# axiom_beta_sensor_cmv12000_tht.net
KiCad netlist of a schematic drawn in EAGLE
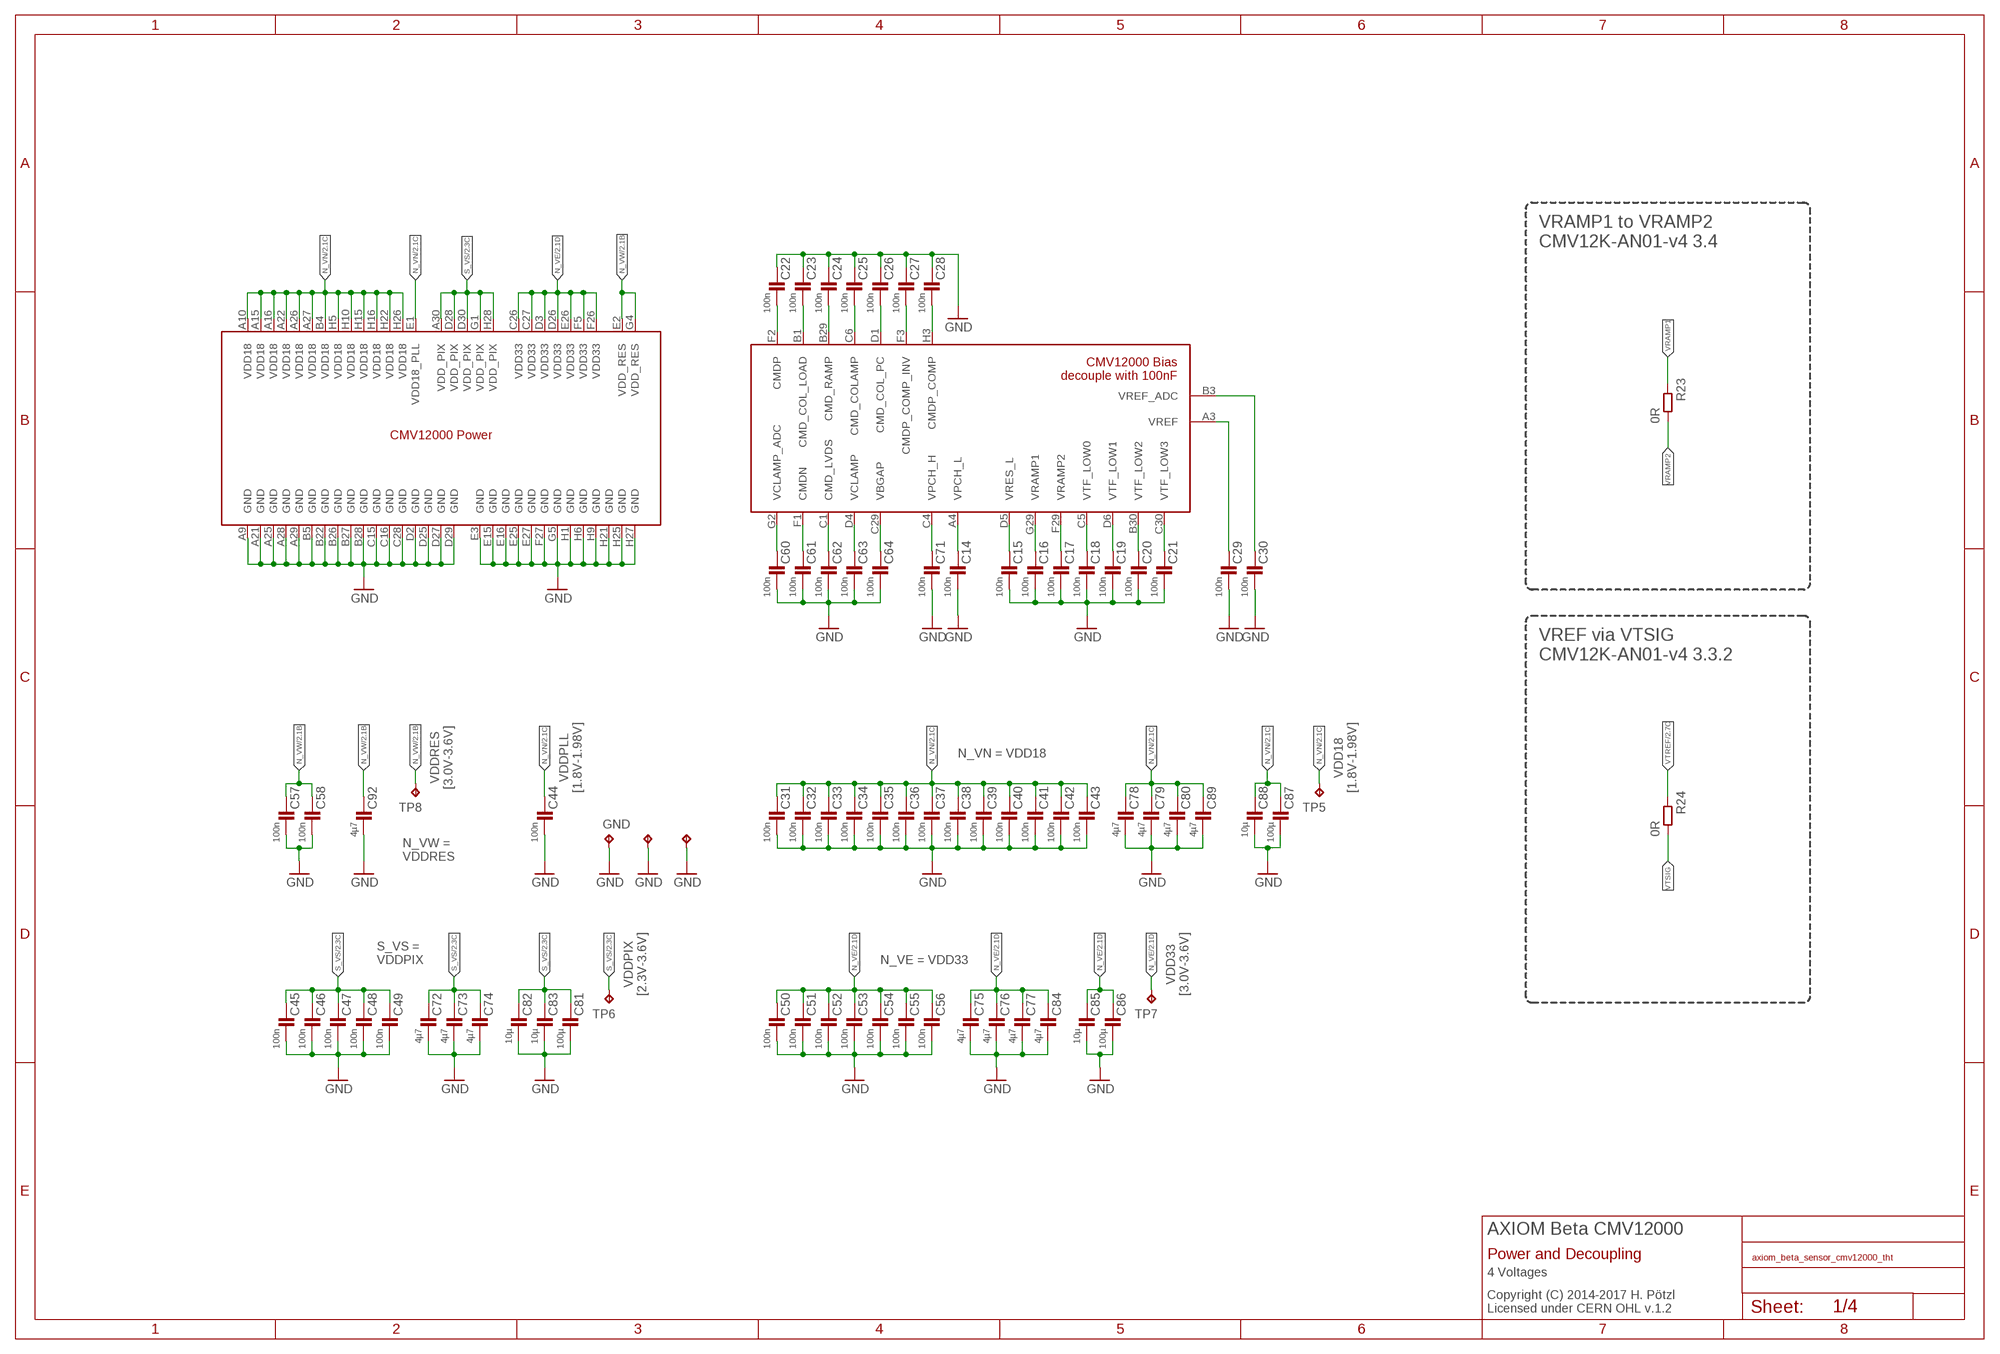
[diagram p0: schematic, sheet 1]
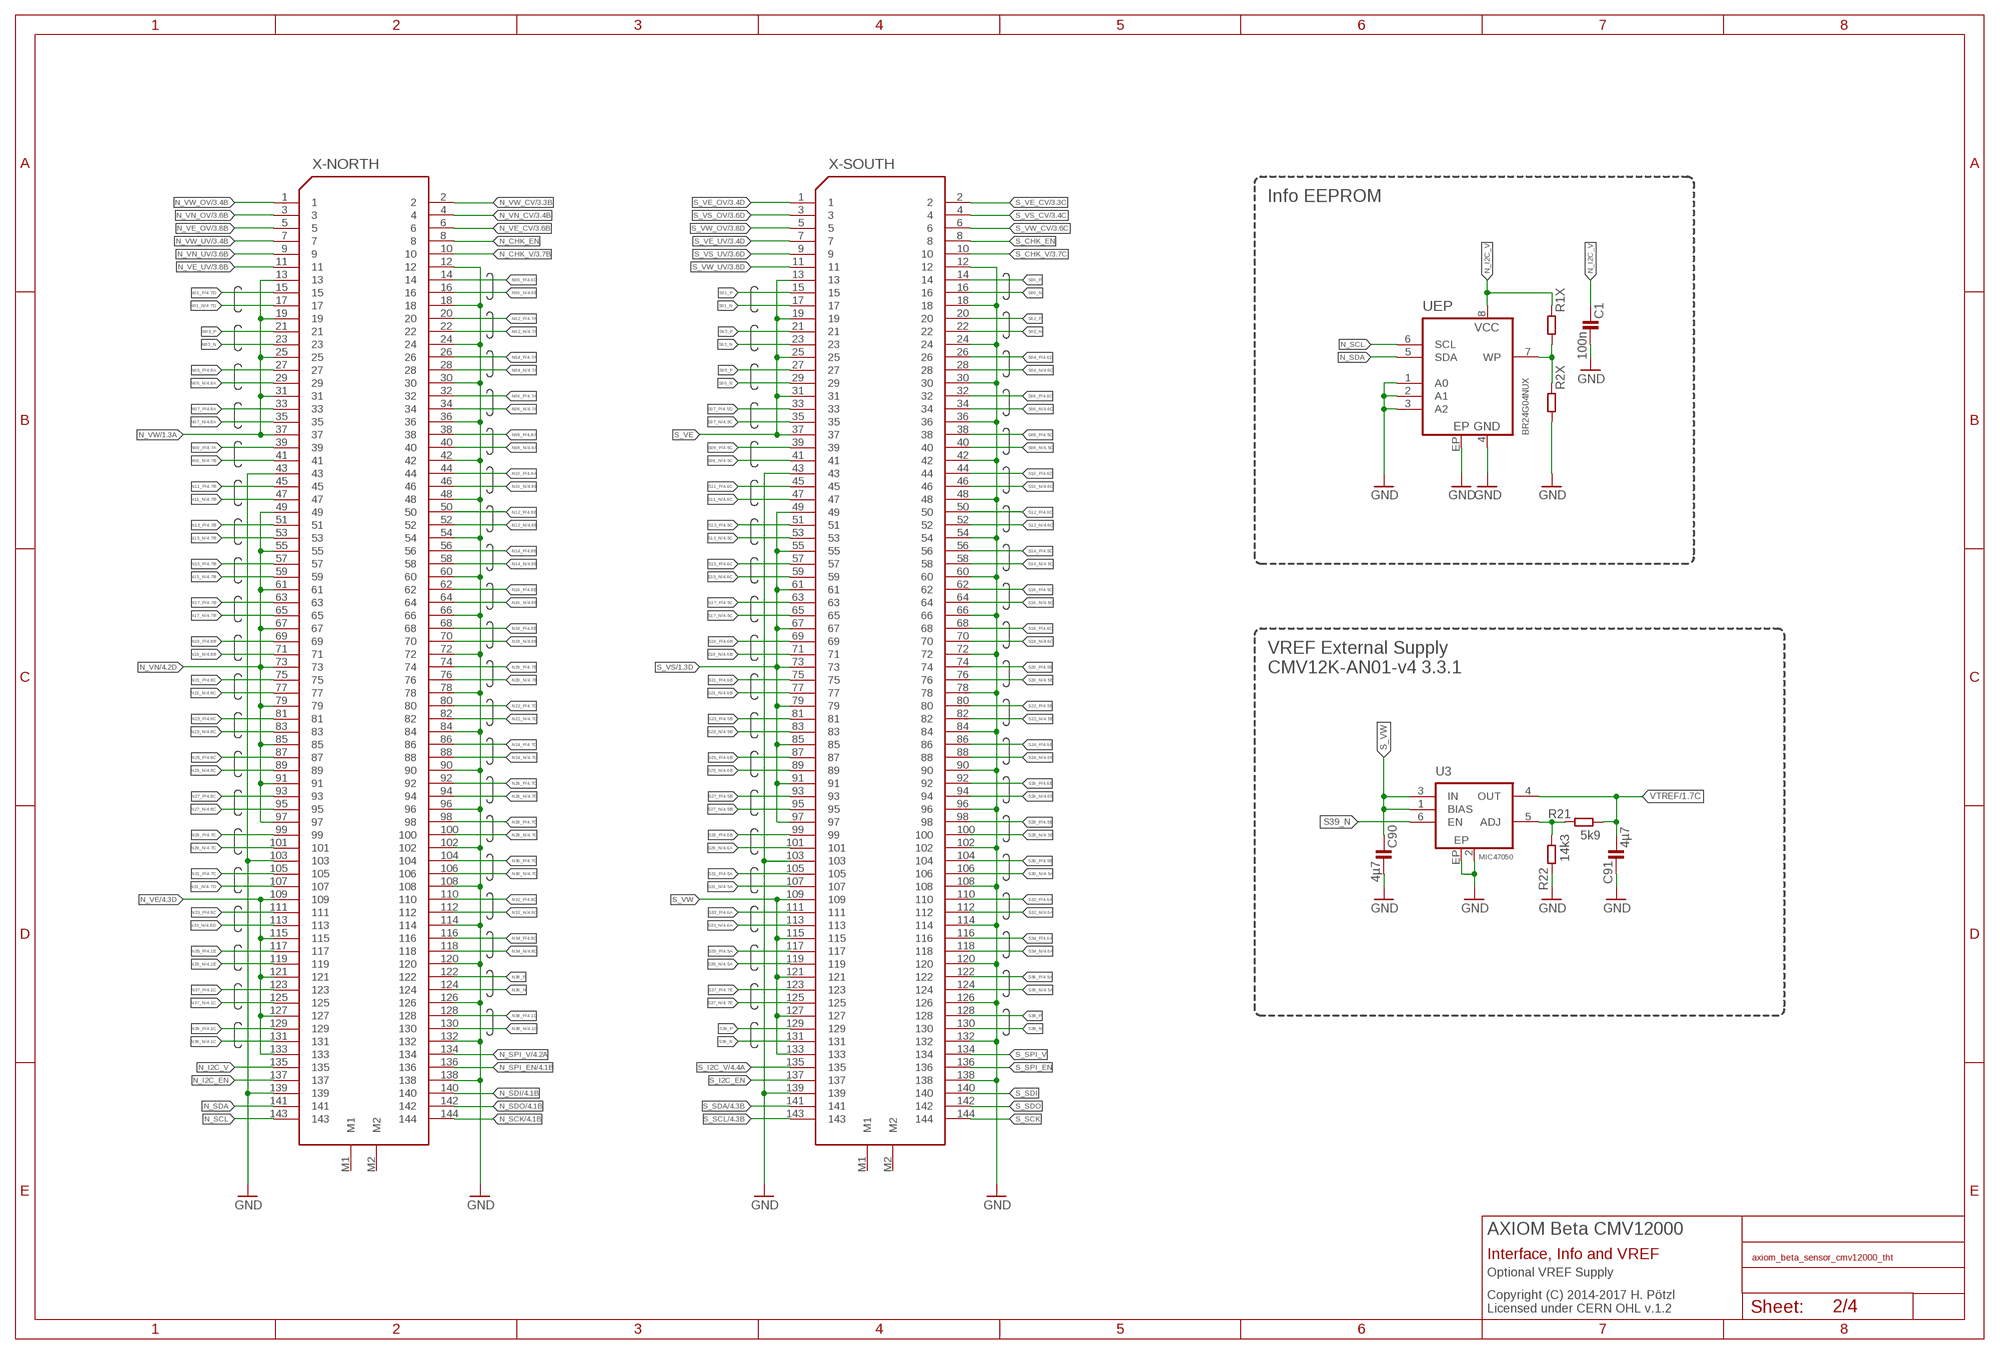
[diagram p1: schematic, sheet 2]
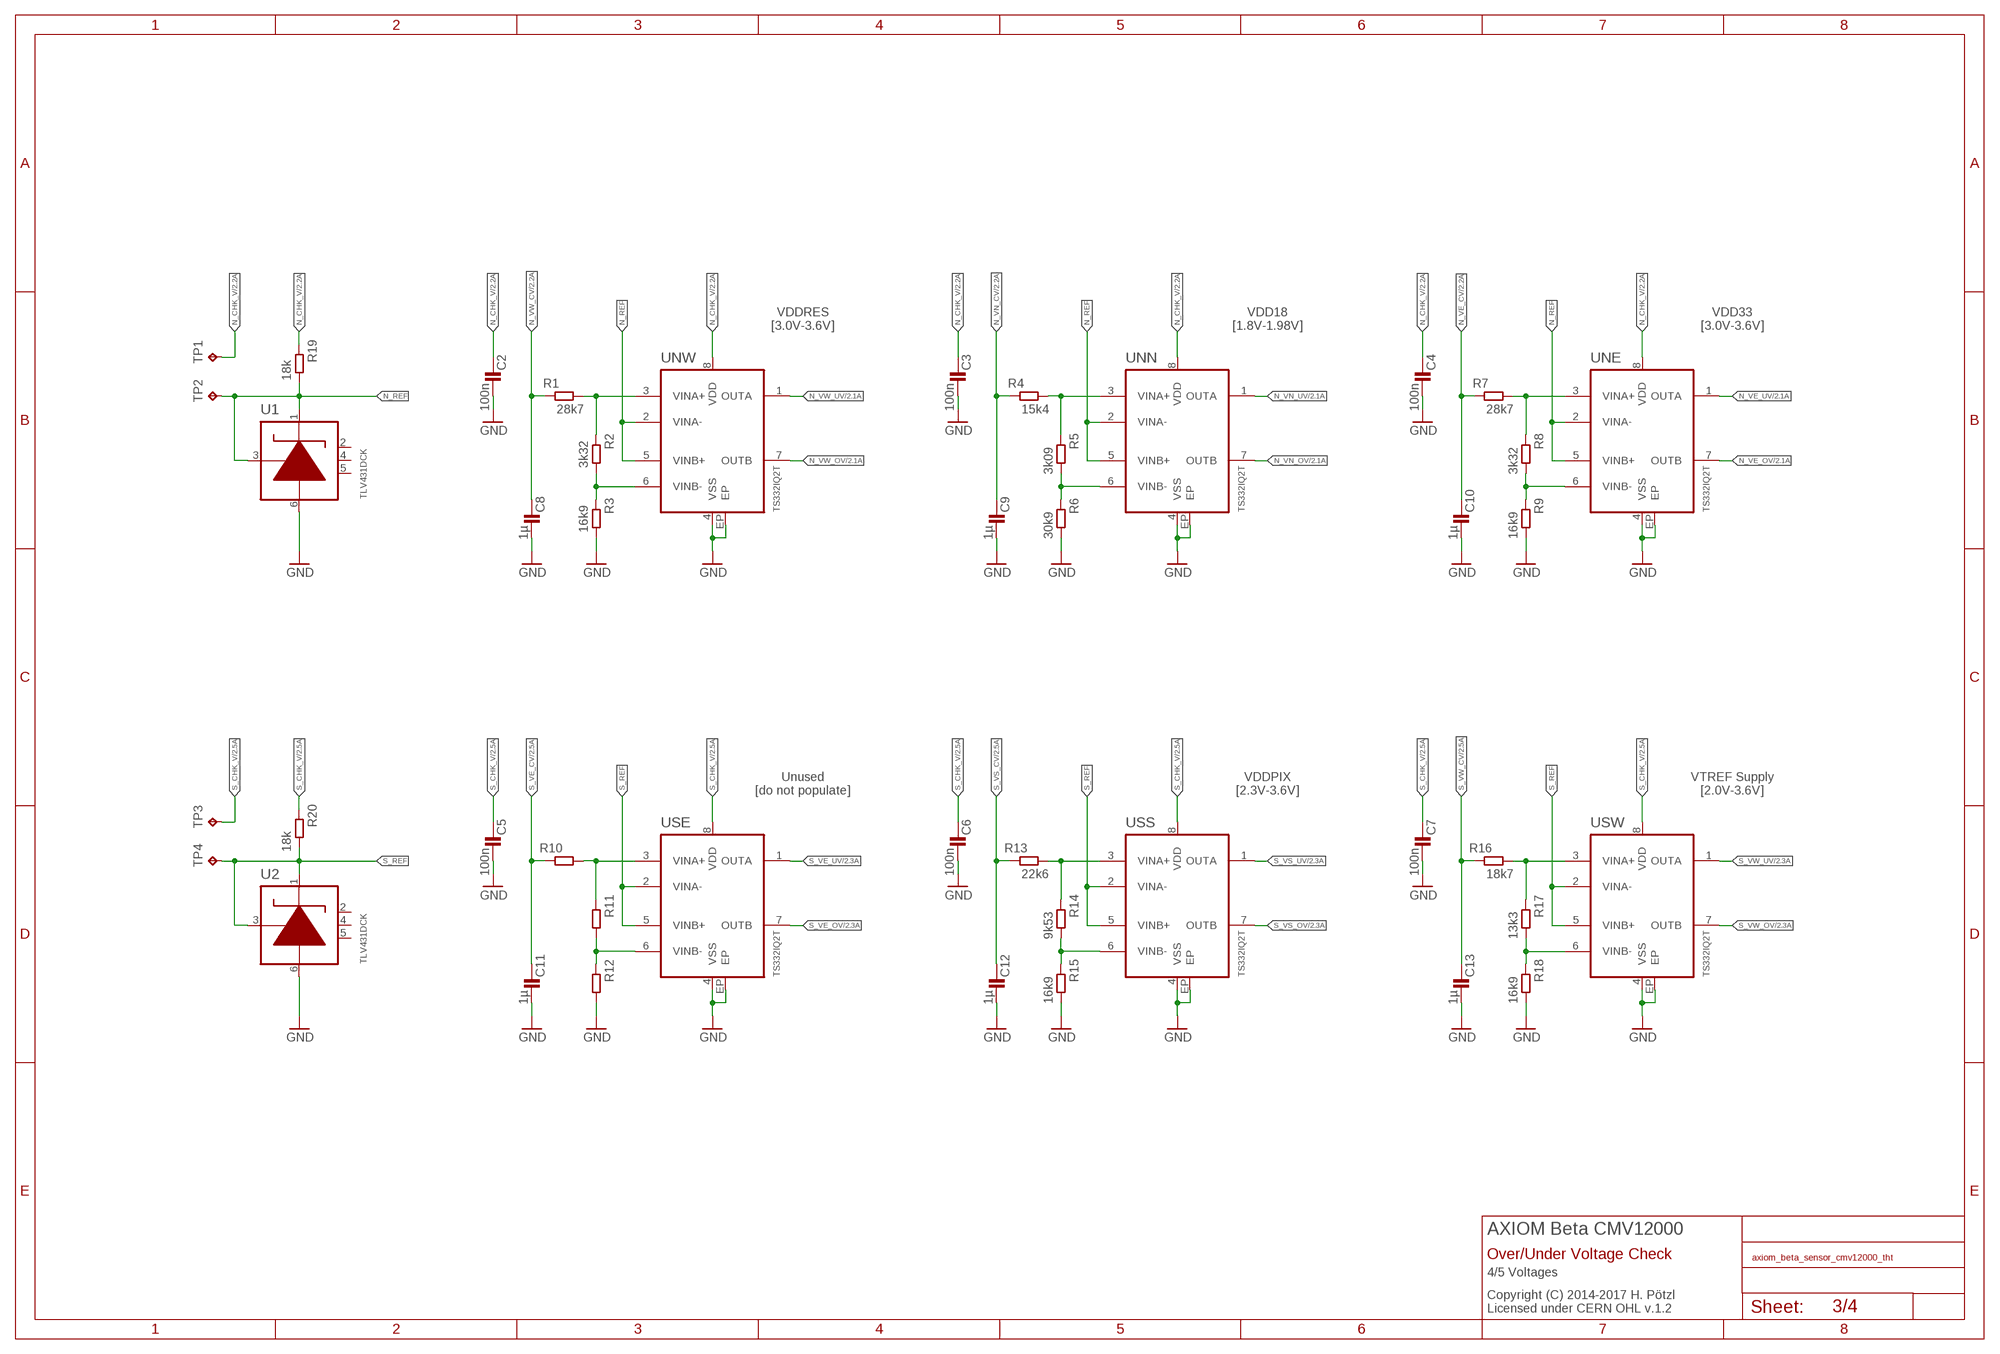
[diagram p2: schematic, sheet 3]
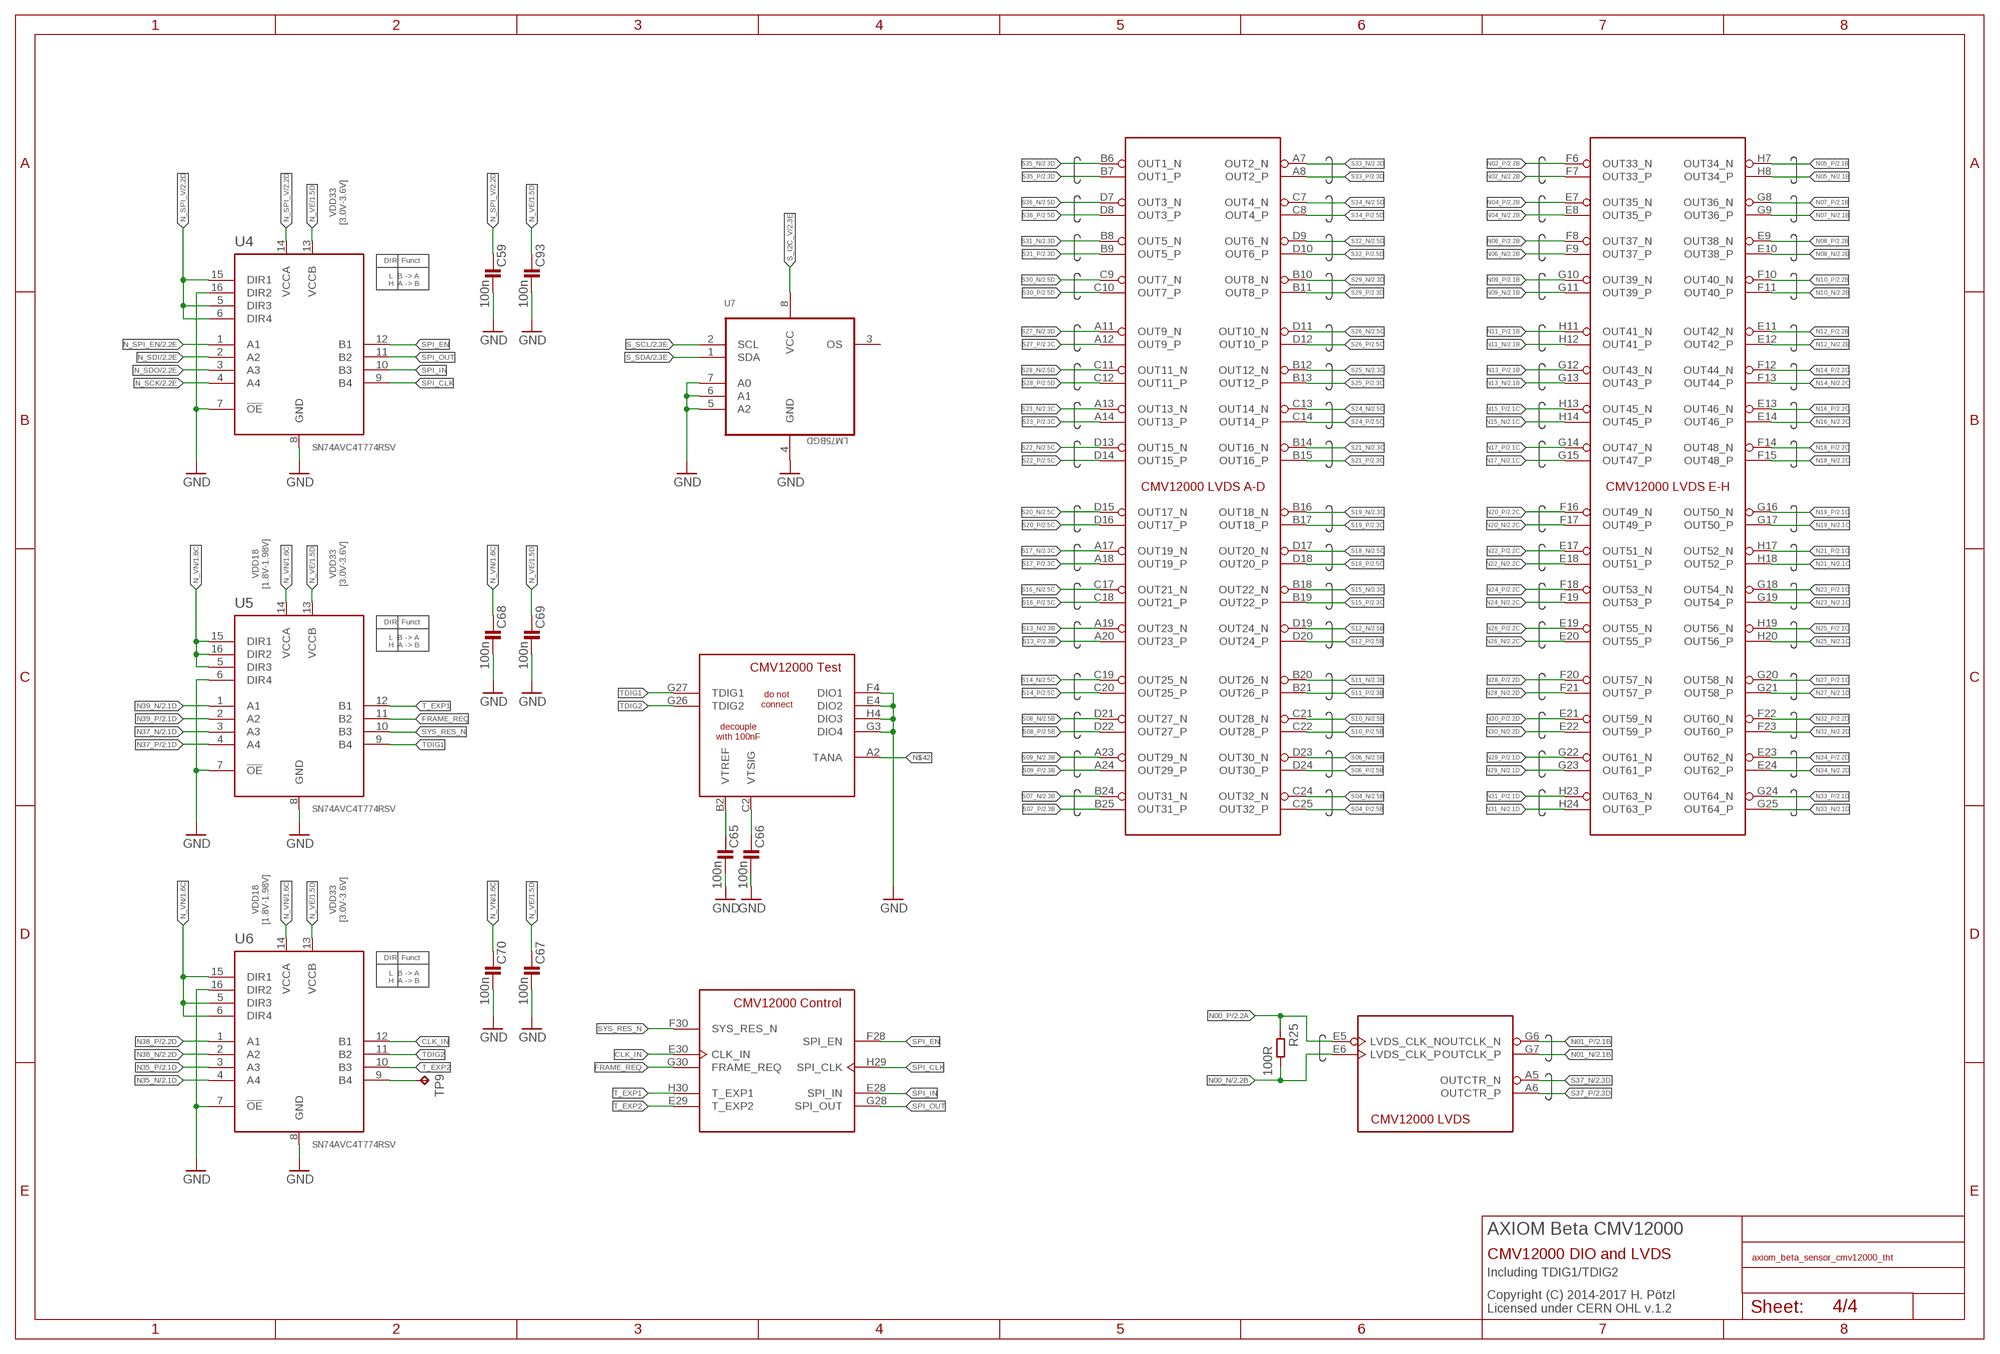
[diagram p3: schematic, sheet 4]

(export (version "E")
  (design (tool "Eeschema 10.0.6"))
  (components
    (comp (ref "C1")
      (value "100n")
      (footprint "eagle-import:0402-C")
      (libsource (lib "eagle-import") (part "C0402-C"))
    )
    (comp (ref "C90")
      (value "4µ7")
      (footprint "eagle-import:0402-C")
      (libsource (lib "eagle-import") (part "C0402-C"))
    )
    (comp (ref "C91")
      (value "4µ7")
      (footprint "eagle-import:0402-C")
      (libsource (lib "eagle-import") (part "C0402-C"))
    )
    (comp (ref "R1X")
      (value "R0402-C")
      (footprint "eagle-import:0402-C")
      (libsource (lib "eagle-import") (part "R0402-C"))
    )
    (comp (ref "R2X")
      (value "R0402-C")
      (footprint "eagle-import:0402-C")
      (libsource (lib "eagle-import") (part "R0402-C"))
    )
    (comp (ref "R21")
      (value "5k9")
      (footprint "eagle-import:0402-C")
      (libsource (lib "eagle-import") (part "R0402-C"))
    )
    (comp (ref "R22")
      (value "14k3")
      (footprint "eagle-import:0402-C")
      (libsource (lib "eagle-import") (part "R0402-C"))
    )
    (comp (ref "U3")
      (value "MIC47050")
      (footprint "eagle-import:MLF-6")
      (libsource (lib "eagle-import") (part "MIC47050-ADJ"))
    )
    (comp (ref "UEP")
      (value "BR24G04NUX")
      (footprint "eagle-import:DFN200X300X100-9N")
      (libsource (lib "eagle-import") (part "BR24G04NUX"))
    )
    (comp (ref "X-NORTH")
      (value "FX10-144P")
      (footprint "eagle-import:FX10A-144P")
      (libsource (lib "eagle-import") (part "FX10-144P"))
    )
    (comp (ref "X-SOUTH")
      (value "FX10-144P")
      (footprint "eagle-import:FX10A-144P")
      (libsource (lib "eagle-import") (part "FX10-144P"))
    )
    (comp (ref "C14")
      (value "100n")
      (footprint "eagle-import:0402-C")
      (libsource (lib "eagle-import") (part "C0402-C"))
    )
    (comp (ref "C15")
      (value "100n")
      (footprint "eagle-import:0402-C")
      (libsource (lib "eagle-import") (part "C0402-C"))
    )
    (comp (ref "C16")
      (value "100n")
      (footprint "eagle-import:0402-C")
      (libsource (lib "eagle-import") (part "C0402-C"))
    )
    (comp (ref "C17")
      (value "100n")
      (footprint "eagle-import:0402-C")
      (libsource (lib "eagle-import") (part "C0402-C"))
    )
    (comp (ref "C18")
      (value "100n")
      (footprint "eagle-import:0402-C")
      (libsource (lib "eagle-import") (part "C0402-C"))
    )
    (comp (ref "C19")
      (value "100n")
      (footprint "eagle-import:0402-C")
      (libsource (lib "eagle-import") (part "C0402-C"))
    )
    (comp (ref "C20")
      (value "100n")
      (footprint "eagle-import:0402-C")
      (libsource (lib "eagle-import") (part "C0402-C"))
    )
    (comp (ref "C21")
      (value "100n")
      (footprint "eagle-import:0402-C")
      (libsource (lib "eagle-import") (part "C0402-C"))
    )
    (comp (ref "C22")
      (value "100n")
      (footprint "eagle-import:0402-C")
      (libsource (lib "eagle-import") (part "C0402-C"))
    )
    (comp (ref "C23")
      (value "100n")
      (footprint "eagle-import:0402-C")
      (libsource (lib "eagle-import") (part "C0402-C"))
    )
    (comp (ref "C24")
      (value "100n")
      (footprint "eagle-import:0402-C")
      (libsource (lib "eagle-import") (part "C0402-C"))
    )
    (comp (ref "C25")
      (value "100n")
      (footprint "eagle-import:0402-C")
      (libsource (lib "eagle-import") (part "C0402-C"))
    )
    (comp (ref "C26")
      (value "100n")
      (footprint "eagle-import:0402-C")
      (libsource (lib "eagle-import") (part "C0402-C"))
    )
    (comp (ref "C27")
      (value "100n")
      (footprint "eagle-import:0402-C")
      (libsource (lib "eagle-import") (part "C0402-C"))
    )
    (comp (ref "C28")
      (value "100n")
      (footprint "eagle-import:0402-C")
      (libsource (lib "eagle-import") (part "C0402-C"))
    )
    (comp (ref "C29")
      (value "100n")
      (footprint "eagle-import:0402-C")
      (libsource (lib "eagle-import") (part "C0402-C"))
    )
    (comp (ref "C30")
      (value "100n")
      (footprint "eagle-import:0402-C")
      (libsource (lib "eagle-import") (part "C0402-C"))
    )
    (comp (ref "C31")
      (value "100n")
      (footprint "eagle-import:0402-C")
      (libsource (lib "eagle-import") (part "C0402-C"))
    )
    (comp (ref "C32")
      (value "100n")
      (footprint "eagle-import:0402-C")
      (libsource (lib "eagle-import") (part "C0402-C"))
    )
    (comp (ref "C33")
      (value "100n")
      (footprint "eagle-import:0402-C")
      (libsource (lib "eagle-import") (part "C0402-C"))
    )
    (comp (ref "C34")
      (value "100n")
      (footprint "eagle-import:0402-C")
      (libsource (lib "eagle-import") (part "C0402-C"))
    )
    (comp (ref "C35")
      (value "100n")
      (footprint "eagle-import:0402-C")
      (libsource (lib "eagle-import") (part "C0402-C"))
    )
    (comp (ref "C36")
      (value "100n")
      (footprint "eagle-import:0402-C")
      (libsource (lib "eagle-import") (part "C0402-C"))
    )
    (comp (ref "C37")
      (value "100n")
      (footprint "eagle-import:0402-C")
      (libsource (lib "eagle-import") (part "C0402-C"))
    )
    (comp (ref "C38")
      (value "100n")
      (footprint "eagle-import:0402-C")
      (libsource (lib "eagle-import") (part "C0402-C"))
    )
    (comp (ref "C39")
      (value "100n")
      (footprint "eagle-import:0402-C")
      (libsource (lib "eagle-import") (part "C0402-C"))
    )
    (comp (ref "C40")
      (value "100n")
      (footprint "eagle-import:0402-C")
      (libsource (lib "eagle-import") (part "C0402-C"))
    )
    (comp (ref "C41")
      (value "100n")
      (footprint "eagle-import:0402-C")
      (libsource (lib "eagle-import") (part "C0402-C"))
    )
    (comp (ref "C42")
      (value "100n")
      (footprint "eagle-import:0402-C")
      (libsource (lib "eagle-import") (part "C0402-C"))
    )
    (comp (ref "C43")
      (value "100n")
      (footprint "eagle-import:0402-C")
      (libsource (lib "eagle-import") (part "C0402-C"))
    )
    (comp (ref "C44")
      (value "100n")
      (footprint "eagle-import:0402-C")
      (libsource (lib "eagle-import") (part "C0402-C"))
    )
    (comp (ref "C45")
      (value "100n")
      (footprint "eagle-import:0402-C")
      (libsource (lib "eagle-import") (part "C0402-C"))
    )
    (comp (ref "C46")
      (value "100n")
      (footprint "eagle-import:0402-C")
      (libsource (lib "eagle-import") (part "C0402-C"))
    )
    (comp (ref "C47")
      (value "100n")
      (footprint "eagle-import:0402-C")
      (libsource (lib "eagle-import") (part "C0402-C"))
    )
    (comp (ref "C48")
      (value "100n")
      (footprint "eagle-import:0402-C")
      (libsource (lib "eagle-import") (part "C0402-C"))
    )
    (comp (ref "C49")
      (value "100n")
      (footprint "eagle-import:0402-C")
      (libsource (lib "eagle-import") (part "C0402-C"))
    )
    (comp (ref "C50")
      (value "100n")
      (footprint "eagle-import:0402-C")
      (libsource (lib "eagle-import") (part "C0402-C"))
    )
    (comp (ref "C51")
      (value "100n")
      (footprint "eagle-import:0402-C")
      (libsource (lib "eagle-import") (part "C0402-C"))
    )
    (comp (ref "C52")
      (value "100n")
      (footprint "eagle-import:0402-C")
      (libsource (lib "eagle-import") (part "C0402-C"))
    )
    (comp (ref "C53")
      (value "100n")
      (footprint "eagle-import:0402-C")
      (libsource (lib "eagle-import") (part "C0402-C"))
    )
    (comp (ref "C54")
      (value "100n")
      (footprint "eagle-import:0402-C")
      (libsource (lib "eagle-import") (part "C0402-C"))
    )
    (comp (ref "C55")
      (value "100n")
      (footprint "eagle-import:0402-C")
      (libsource (lib "eagle-import") (part "C0402-C"))
    )
    (comp (ref "C56")
      (value "100n")
      (footprint "eagle-import:0402-C")
      (libsource (lib "eagle-import") (part "C0402-C"))
    )
    (comp (ref "C57")
      (value "100n")
      (footprint "eagle-import:0402-C")
      (libsource (lib "eagle-import") (part "C0402-C"))
    )
    (comp (ref "C58")
      (value "100n")
      (footprint "eagle-import:0402-C")
      (libsource (lib "eagle-import") (part "C0402-C"))
    )
    (comp (ref "C60")
      (value "100n")
      (footprint "eagle-import:0402-C")
      (libsource (lib "eagle-import") (part "C0402-C"))
    )
    (comp (ref "C61")
      (value "100n")
      (footprint "eagle-import:0402-C")
      (libsource (lib "eagle-import") (part "C0402-C"))
    )
    (comp (ref "C62")
      (value "100n")
      (footprint "eagle-import:0402-C")
      (libsource (lib "eagle-import") (part "C0402-C"))
    )
    (comp (ref "C63")
      (value "100n")
      (footprint "eagle-import:0402-C")
      (libsource (lib "eagle-import") (part "C0402-C"))
    )
    (comp (ref "C64")
      (value "100n")
      (footprint "eagle-import:0402-C")
      (libsource (lib "eagle-import") (part "C0402-C"))
    )
    (comp (ref "C71")
      (value "100n")
      (footprint "eagle-import:0402-C")
      (libsource (lib "eagle-import") (part "C0402-C"))
    )
    (comp (ref "C72")
      (value "4µ7")
      (footprint "eagle-import:0402-B")
      (libsource (lib "eagle-import") (part "C0402-B"))
    )
    (comp (ref "C73")
      (value "4µ7")
      (footprint "eagle-import:0402-C")
      (libsource (lib "eagle-import") (part "C0402-C"))
    )
    (comp (ref "C74")
      (value "4µ7")
      (footprint "eagle-import:0402-C")
      (libsource (lib "eagle-import") (part "C0402-C"))
    )
    (comp (ref "C75")
      (value "4µ7")
      (footprint "eagle-import:0402-C")
      (libsource (lib "eagle-import") (part "C0402-C"))
    )
    (comp (ref "C76")
      (value "4µ7")
      (footprint "eagle-import:0402-C")
      (libsource (lib "eagle-import") (part "C0402-C"))
    )
    (comp (ref "C77")
      (value "4µ7")
      (footprint "eagle-import:0402-B")
      (libsource (lib "eagle-import") (part "C0402-B"))
    )
    (comp (ref "C78")
      (value "4µ7")
      (footprint "eagle-import:0402-B")
      (libsource (lib "eagle-import") (part "C0402-B"))
    )
    (comp (ref "C79")
      (value "4µ7")
      (footprint "eagle-import:0402-C")
      (libsource (lib "eagle-import") (part "C0402-C"))
    )
    (comp (ref "C80")
      (value "4µ7")
      (footprint "eagle-import:0402-C")
      (libsource (lib "eagle-import") (part "C0402-C"))
    )
    (comp (ref "C81")
      (value "100µ")
      (footprint "eagle-import:1206-B")
      (libsource (lib "eagle-import") (part "C1206-B"))
    )
    (comp (ref "C82")
      (value "10µ")
      (footprint "eagle-import:0603-C")
      (libsource (lib "eagle-import") (part "C0603-C"))
    )
    (comp (ref "C83")
      (value "10µ")
      (footprint "eagle-import:0603-C")
      (libsource (lib "eagle-import") (part "C0603-C"))
    )
    (comp (ref "C84")
      (value "4µ7")
      (footprint "eagle-import:0402-C")
      (libsource (lib "eagle-import") (part "C0402-C"))
    )
    (comp (ref "C85")
      (value "10µ")
      (footprint "eagle-import:0603-C")
      (libsource (lib "eagle-import") (part "C0603-C"))
    )
    (comp (ref "C86")
      (value "100µ")
      (footprint "eagle-import:1206-B")
      (libsource (lib "eagle-import") (part "C1206-B"))
    )
    (comp (ref "C87")
      (value "100µ")
      (footprint "eagle-import:1206-B")
      (libsource (lib "eagle-import") (part "C1206-B"))
    )
    (comp (ref "C88")
      (value "10µ")
      (footprint "eagle-import:0603-C")
      (libsource (lib "eagle-import") (part "C0603-C"))
    )
    (comp (ref "C89")
      (value "4µ7")
      (footprint "eagle-import:0402-C")
      (libsource (lib "eagle-import") (part "C0402-C"))
    )
    (comp (ref "C92")
      (value "4µ7")
      (footprint "eagle-import:0402-C")
      (libsource (lib "eagle-import") (part "C0402-C"))
    )
    (comp (ref "GND")
      (value "TPTP10R")
      (footprint "eagle-import:TP10R")
      (libsource (lib "eagle-import") (part "TPTP10R"))
    )
    (comp (ref "GND75")
      (value "TPTP10R")
      (footprint "eagle-import:TP10R")
      (libsource (lib "eagle-import") (part "TPTP10R"))
    )
    (comp (ref "GND77")
      (value "TPTP10R")
      (footprint "eagle-import:TP10R")
      (libsource (lib "eagle-import") (part "TPTP10R"))
    )
    (comp (ref "R23")
      (value "0R")
      (footprint "eagle-import:0402-C")
      (libsource (lib "eagle-import") (part "R0402-C"))
    )
    (comp (ref "R24")
      (value "0R")
      (footprint "eagle-import:0402-C")
      (libsource (lib "eagle-import") (part "R0402-C"))
    )
    (comp (ref "SENSOR")
      (value "CMV12000ANDON-CREAM")
      (footprint "eagle-import:10-30-07-237-400T4-CREAM")
      (libsource (lib "eagle-import") (part "CMV12000ANDON-CREAM"))
    )
    (comp (ref "TP5")
      (value "TPTP10R")
      (footprint "eagle-import:TP10R")
      (libsource (lib "eagle-import") (part "TPTP10R"))
    )
    (comp (ref "TP6")
      (value "TPTP10R")
      (footprint "eagle-import:TP10R")
      (libsource (lib "eagle-import") (part "TPTP10R"))
    )
    (comp (ref "TP7")
      (value "TPTP10R")
      (footprint "eagle-import:TP10R")
      (libsource (lib "eagle-import") (part "TPTP10R"))
    )
    (comp (ref "TP8")
      (value "TPTP10R")
      (footprint "eagle-import:TP10R")
      (libsource (lib "eagle-import") (part "TPTP10R"))
    )
    (comp (ref "C2")
      (value "100n")
      (footprint "eagle-import:0402-C")
      (libsource (lib "eagle-import") (part "C0402-C"))
    )
    (comp (ref "C3")
      (value "100n")
      (footprint "eagle-import:0402-C")
      (libsource (lib "eagle-import") (part "C0402-C"))
    )
    (comp (ref "C4")
      (value "100n")
      (footprint "eagle-import:0402-C")
      (libsource (lib "eagle-import") (part "C0402-C"))
    )
    (comp (ref "C5")
      (value "100n")
      (footprint "eagle-import:0402-C")
      (libsource (lib "eagle-import") (part "C0402-C"))
    )
    (comp (ref "C6")
      (value "100n")
      (footprint "eagle-import:0402-C")
      (libsource (lib "eagle-import") (part "C0402-C"))
    )
    (comp (ref "C7")
      (value "100n")
      (footprint "eagle-import:0402-C")
      (libsource (lib "eagle-import") (part "C0402-C"))
    )
    (comp (ref "C8")
      (value "1µ")
      (footprint "eagle-import:0402-C")
      (libsource (lib "eagle-import") (part "C0402-C"))
    )
    (comp (ref "C9")
      (value "1µ")
      (footprint "eagle-import:0402-C")
      (libsource (lib "eagle-import") (part "C0402-C"))
    )
    (comp (ref "C10")
      (value "1µ")
      (footprint "eagle-import:0402-C")
      (libsource (lib "eagle-import") (part "C0402-C"))
    )
    (comp (ref "C11")
      (value "1µ")
      (footprint "eagle-import:0402-C")
      (libsource (lib "eagle-import") (part "C0402-C"))
    )
    (comp (ref "C12")
      (value "1µ")
      (footprint "eagle-import:0402-C")
      (libsource (lib "eagle-import") (part "C0402-C"))
    )
    (comp (ref "C13")
      (value "1µ")
      (footprint "eagle-import:0402-C")
      (libsource (lib "eagle-import") (part "C0402-C"))
    )
    (comp (ref "R1")
      (value "28k7")
      (footprint "eagle-import:0402-C")
      (libsource (lib "eagle-import") (part "R0402-C"))
    )
    (comp (ref "R2")
      (value "3k32")
      (footprint "eagle-import:0402-C")
      (libsource (lib "eagle-import") (part "R0402-C"))
    )
    (comp (ref "R3")
      (value "16k9")
      (footprint "eagle-import:0402-C")
      (libsource (lib "eagle-import") (part "R0402-C"))
    )
    (comp (ref "R4")
      (value "15k4")
      (footprint "eagle-import:0402-C")
      (libsource (lib "eagle-import") (part "R0402-C"))
    )
    (comp (ref "R5")
      (value "3k09")
      (footprint "eagle-import:0402-C")
      (libsource (lib "eagle-import") (part "R0402-C"))
    )
    (comp (ref "R6")
      (value "30k9")
      (footprint "eagle-import:0402-C")
      (libsource (lib "eagle-import") (part "R0402-C"))
    )
    (comp (ref "R7")
      (value "28k7")
      (footprint "eagle-import:0402-C")
      (libsource (lib "eagle-import") (part "R0402-C"))
    )
    (comp (ref "R8")
      (value "3k32")
      (footprint "eagle-import:0402-C")
      (libsource (lib "eagle-import") (part "R0402-C"))
    )
    (comp (ref "R9")
      (value "16k9")
      (footprint "eagle-import:0402-C")
      (libsource (lib "eagle-import") (part "R0402-C"))
    )
    (comp (ref "R10")
      (value "R0402-C")
      (footprint "eagle-import:0402-C")
      (libsource (lib "eagle-import") (part "R0402-C"))
    )
    (comp (ref "R11")
      (value "R0402-C")
      (footprint "eagle-import:0402-C")
      (libsource (lib "eagle-import") (part "R0402-C"))
    )
    (comp (ref "R12")
      (value "R0402-C")
      (footprint "eagle-import:0402-C")
      (libsource (lib "eagle-import") (part "R0402-C"))
    )
    (comp (ref "R13")
      (value "22k6")
      (footprint "eagle-import:0402-C")
      (libsource (lib "eagle-import") (part "R0402-C"))
    )
    (comp (ref "R14")
      (value "9k53")
      (footprint "eagle-import:0402-C")
      (libsource (lib "eagle-import") (part "R0402-C"))
    )
    (comp (ref "R15")
      (value "16k9")
      (footprint "eagle-import:0402-C")
      (libsource (lib "eagle-import") (part "R0402-C"))
    )
    (comp (ref "R16")
      (value "18k7")
      (footprint "eagle-import:0402-C")
      (libsource (lib "eagle-import") (part "R0402-C"))
    )
    (comp (ref "R17")
      (value "13k3")
      (footprint "eagle-import:0402-C")
      (libsource (lib "eagle-import") (part "R0402-C"))
    )
    (comp (ref "R18")
      (value "16k9")
      (footprint "eagle-import:0402-C")
      (libsource (lib "eagle-import") (part "R0402-C"))
    )
    (comp (ref "R19")
      (value "18k")
      (footprint "eagle-import:0402-C")
      (libsource (lib "eagle-import") (part "R0402-C"))
    )
    (comp (ref "R20")
      (value "18k")
      (footprint "eagle-import:0402-C")
      (libsource (lib "eagle-import") (part "R0402-C"))
    )
    (comp (ref "TP1")
      (value "TPTP10R")
      (footprint "eagle-import:TP10R")
      (libsource (lib "eagle-import") (part "TPTP10R"))
    )
    (comp (ref "TP2")
      (value "TPTP10R")
      (footprint "eagle-import:TP10R")
      (libsource (lib "eagle-import") (part "TPTP10R"))
    )
    (comp (ref "TP3")
      (value "TPTP10R")
      (footprint "eagle-import:TP10R")
      (libsource (lib "eagle-import") (part "TPTP10R"))
    )
    (comp (ref "TP4")
      (value "TPTP10R")
      (footprint "eagle-import:TP10R")
      (libsource (lib "eagle-import") (part "TPTP10R"))
    )
    (comp (ref "U1")
      (value "TLV431DCK")
      (footprint "eagle-import:SOT65P210X110-6N")
      (libsource (lib "eagle-import") (part "TLV431DCK"))
    )
    (comp (ref "U2")
      (value "TLV431DCK")
      (footprint "eagle-import:SOT65P210X110-6N")
      (libsource (lib "eagle-import") (part "TLV431DCK"))
    )
    (comp (ref "UNE")
      (value "TS332IQ2T")
      (footprint "eagle-import:DFN200X200X100-9N")
      (libsource (lib "eagle-import") (part "TS332IQ2T"))
    )
    (comp (ref "UNN")
      (value "TS332IQ2T")
      (footprint "eagle-import:DFN200X200X100-9N")
      (libsource (lib "eagle-import") (part "TS332IQ2T"))
    )
    (comp (ref "UNW")
      (value "TS332IQ2T")
      (footprint "eagle-import:DFN200X200X100-9N")
      (libsource (lib "eagle-import") (part "TS332IQ2T"))
    )
    (comp (ref "USE")
      (value "TS332IQ2T")
      (footprint "eagle-import:DFN200X200X100-9N")
      (libsource (lib "eagle-import") (part "TS332IQ2T"))
    )
    (comp (ref "USS")
      (value "TS332IQ2T")
      (footprint "eagle-import:DFN200X200X100-9N")
      (libsource (lib "eagle-import") (part "TS332IQ2T"))
    )
    (comp (ref "USW")
      (value "TS332IQ2T")
      (footprint "eagle-import:DFN200X200X100-9N")
      (libsource (lib "eagle-import") (part "TS332IQ2T"))
    )
    (comp (ref "C59")
      (value "100n")
      (footprint "eagle-import:0402-C")
      (libsource (lib "eagle-import") (part "C0402-C"))
    )
    (comp (ref "C65")
      (value "100n")
      (footprint "eagle-import:0402-C")
      (libsource (lib "eagle-import") (part "C0402-C"))
    )
    (comp (ref "C66")
      (value "100n")
      (footprint "eagle-import:0402-C")
      (libsource (lib "eagle-import") (part "C0402-C"))
    )
    (comp (ref "C67")
      (value "100n")
      (footprint "eagle-import:0402-C")
      (libsource (lib "eagle-import") (part "C0402-C"))
    )
    (comp (ref "C68")
      (value "100n")
      (footprint "eagle-import:0402-C")
      (libsource (lib "eagle-import") (part "C0402-C"))
    )
    (comp (ref "C69")
      (value "100n")
      (footprint "eagle-import:0402-C")
      (libsource (lib "eagle-import") (part "C0402-C"))
    )
    (comp (ref "C70")
      (value "100n")
      (footprint "eagle-import:0402-C")
      (libsource (lib "eagle-import") (part "C0402-C"))
    )
    (comp (ref "C93")
      (value "100n")
      (footprint "eagle-import:0402-C")
      (libsource (lib "eagle-import") (part "C0402-C"))
    )
    (comp (ref "R25")
      (value "100R")
      (footprint "eagle-import:0402-C")
      (libsource (lib "eagle-import") (part "R0402-C"))
    )
    (comp (ref "TP9")
      (value "TPTP10R")
      (footprint "eagle-import:TP10R")
      (libsource (lib "eagle-import") (part "TPTP10R"))
    )
    (comp (ref "U4")
      (value "SN74AVC4T774RSV")
      (footprint "eagle-import:QFN40P185X265X55-16N")
      (libsource (lib "eagle-import") (part "SN74AVC4T774RSV"))
    )
    (comp (ref "U5")
      (value "SN74AVC4T774RSV")
      (footprint "eagle-import:QFN40P185X265X55-16N")
      (libsource (lib "eagle-import") (part "SN74AVC4T774RSV"))
    )
    (comp (ref "U6")
      (value "SN74AVC4T774RSV")
      (footprint "eagle-import:QFN40P185X265X55-16N")
      (libsource (lib "eagle-import") (part "SN74AVC4T774RSV"))
    )
    (comp (ref "U7")
      (value "LM75BGD")
      (footprint "eagle-import:SOT996-2_3")
      (libsource (lib "eagle-import") (part "LM75BGD"))
    )
  )
  (nets
    (net (code "1") (name "CLK_IN") (class "Default")
      (node (ref "SENSOR") (pin "E30") (pinfunction "CLK_IN_E30") (pintype "input"))
      (node (ref "U6") (pin "12") (pinfunction "B1_12") (pintype "bidirectional"))
    )
    (net (code "2") (name "FRAME_REQ") (class "Default")
      (node (ref "SENSOR") (pin "G30") (pinfunction "FRAME_REQ_G30") (pintype "input"))
      (node (ref "U5") (pin "11") (pinfunction "B2_11") (pintype "bidirectional"))
    )
    (net (code "3") (name "GND") (class "Default")
      (node (ref "C1") (pin "2") (pinfunction "2_2") (pintype "passive"))
      (node (ref "C10") (pin "2") (pinfunction "2_2") (pintype "passive"))
      (node (ref "C11") (pin "2") (pinfunction "2_2") (pintype "passive"))
      (node (ref "C12") (pin "2") (pinfunction "2_2") (pintype "passive"))
      (node (ref "C13") (pin "2") (pinfunction "2_2") (pintype "passive"))
      (node (ref "C14") (pin "2") (pinfunction "2_2") (pintype "passive"))
      (node (ref "C15") (pin "2") (pinfunction "2_2") (pintype "passive"))
      (node (ref "C16") (pin "2") (pinfunction "2_2") (pintype "passive"))
      (node (ref "C17") (pin "2") (pinfunction "2_2") (pintype "passive"))
      (node (ref "C18") (pin "2") (pinfunction "2_2") (pintype "passive"))
      (node (ref "C19") (pin "2") (pinfunction "2_2") (pintype "passive"))
      (node (ref "C2") (pin "2") (pinfunction "2_2") (pintype "passive"))
      (node (ref "C20") (pin "2") (pinfunction "2_2") (pintype "passive"))
      (node (ref "C21") (pin "2") (pinfunction "2_2") (pintype "passive"))
      (node (ref "C22") (pin "1") (pinfunction "1_1") (pintype "passive"))
      (node (ref "C23") (pin "1") (pinfunction "1_1") (pintype "passive"))
      (node (ref "C24") (pin "1") (pinfunction "1_1") (pintype "passive"))
      (node (ref "C25") (pin "1") (pinfunction "1_1") (pintype "passive"))
      (node (ref "C26") (pin "1") (pinfunction "1_1") (pintype "passive"))
      (node (ref "C27") (pin "1") (pinfunction "1_1") (pintype "passive"))
      (node (ref "C28") (pin "1") (pinfunction "1_1") (pintype "passive"))
      (node (ref "C29") (pin "2") (pinfunction "2_2") (pintype "passive"))
      (node (ref "C3") (pin "2") (pinfunction "2_2") (pintype "passive"))
      (node (ref "C30") (pin "2") (pinfunction "2_2") (pintype "passive"))
      (node (ref "C31") (pin "2") (pinfunction "2_2") (pintype "passive"))
      (node (ref "C32") (pin "2") (pinfunction "2_2") (pintype "passive"))
      (node (ref "C33") (pin "2") (pinfunction "2_2") (pintype "passive"))
      (node (ref "C34") (pin "2") (pinfunction "2_2") (pintype "passive"))
      (node (ref "C35") (pin "2") (pinfunction "2_2") (pintype "passive"))
      (node (ref "C36") (pin "2") (pinfunction "2_2") (pintype "passive"))
      (node (ref "C37") (pin "2") (pinfunction "2_2") (pintype "passive"))
      (node (ref "C38") (pin "2") (pinfunction "2_2") (pintype "passive"))
      (node (ref "C39") (pin "2") (pinfunction "2_2") (pintype "passive"))
      (node (ref "C4") (pin "2") (pinfunction "2_2") (pintype "passive"))
      (node (ref "C40") (pin "2") (pinfunction "2_2") (pintype "passive"))
      (node (ref "C41") (pin "2") (pinfunction "2_2") (pintype "passive"))
      (node (ref "C42") (pin "2") (pinfunction "2_2") (pintype "passive"))
      (node (ref "C43") (pin "2") (pinfunction "2_2") (pintype "passive"))
      (node (ref "C44") (pin "2") (pinfunction "2_2") (pintype "passive"))
      (node (ref "C45") (pin "2") (pinfunction "2_2") (pintype "passive"))
      (node (ref "C46") (pin "2") (pinfunction "2_2") (pintype "passive"))
      (node (ref "C47") (pin "2") (pinfunction "2_2") (pintype "passive"))
      (node (ref "C48") (pin "2") (pinfunction "2_2") (pintype "passive"))
      (node (ref "C49") (pin "2") (pinfunction "2_2") (pintype "passive"))
      (node (ref "C5") (pin "2") (pinfunction "2_2") (pintype "passive"))
      (node (ref "C50") (pin "2") (pinfunction "2_2") (pintype "passive"))
      (node (ref "C51") (pin "2") (pinfunction "2_2") (pintype "passive"))
      (node (ref "C52") (pin "2") (pinfunction "2_2") (pintype "passive"))
      (node (ref "C53") (pin "2") (pinfunction "2_2") (pintype "passive"))
      (node (ref "C54") (pin "2") (pinfunction "2_2") (pintype "passive"))
      (node (ref "C55") (pin "2") (pinfunction "2_2") (pintype "passive"))
      (node (ref "C56") (pin "2") (pinfunction "2_2") (pintype "passive"))
      (node (ref "C57") (pin "2") (pinfunction "2_2") (pintype "passive"))
      (node (ref "C58") (pin "2") (pinfunction "2_2") (pintype "passive"))
      (node (ref "C59") (pin "2") (pinfunction "2_2") (pintype "passive"))
      (node (ref "C6") (pin "2") (pinfunction "2_2") (pintype "passive"))
      (node (ref "C60") (pin "2") (pinfunction "2_2") (pintype "passive"))
      (node (ref "C61") (pin "2") (pinfunction "2_2") (pintype "passive"))
      (node (ref "C62") (pin "2") (pinfunction "2_2") (pintype "passive"))
      (node (ref "C63") (pin "2") (pinfunction "2_2") (pintype "passive"))
      (node (ref "C64") (pin "2") (pinfunction "2_2") (pintype "passive"))
      (node (ref "C65") (pin "2") (pinfunction "2_2") (pintype "passive"))
      (node (ref "C66") (pin "2") (pinfunction "2_2") (pintype "passive"))
      (node (ref "C67") (pin "2") (pinfunction "2_2") (pintype "passive"))
      (node (ref "C68") (pin "2") (pinfunction "2_2") (pintype "passive"))
      (node (ref "C69") (pin "2") (pinfunction "2_2") (pintype "passive"))
      (node (ref "C7") (pin "2") (pinfunction "2_2") (pintype "passive"))
      (node (ref "C70") (pin "2") (pinfunction "2_2") (pintype "passive"))
      (node (ref "C71") (pin "2") (pinfunction "2_2") (pintype "passive"))
      (node (ref "C72") (pin "2") (pinfunction "2_2") (pintype "passive"))
      (node (ref "C73") (pin "2") (pinfunction "2_2") (pintype "passive"))
      (node (ref "C74") (pin "2") (pinfunction "2_2") (pintype "passive"))
      (node (ref "C75") (pin "2") (pinfunction "2_2") (pintype "passive"))
      (node (ref "C76") (pin "2") (pinfunction "2_2") (pintype "passive"))
      (node (ref "C77") (pin "2") (pinfunction "2_2") (pintype "passive"))
      (node (ref "C78") (pin "2") (pinfunction "2_2") (pintype "passive"))
      (node (ref "C79") (pin "2") (pinfunction "2_2") (pintype "passive"))
      (node (ref "C8") (pin "2") (pinfunction "2_2") (pintype "passive"))
      (node (ref "C80") (pin "2") (pinfunction "2_2") (pintype "passive"))
      (node (ref "C81") (pin "2") (pinfunction "2_2") (pintype "passive"))
      (node (ref "C82") (pin "2") (pinfunction "2_2") (pintype "passive"))
      (node (ref "C83") (pin "2") (pinfunction "2_2") (pintype "passive"))
      (node (ref "C84") (pin "2") (pinfunction "2_2") (pintype "passive"))
      (node (ref "C85") (pin "2") (pinfunction "2_2") (pintype "passive"))
      (node (ref "C86") (pin "2") (pinfunction "2_2") (pintype "passive"))
      (node (ref "C87") (pin "2") (pinfunction "2_2") (pintype "passive"))
      (node (ref "C88") (pin "2") (pinfunction "2_2") (pintype "passive"))
      (node (ref "C89") (pin "2") (pinfunction "2_2") (pintype "passive"))
      (node (ref "C9") (pin "2") (pinfunction "2_2") (pintype "passive"))
      (node (ref "C90") (pin "2") (pinfunction "2_2") (pintype "passive"))
      (node (ref "C91") (pin "1") (pinfunction "1_1") (pintype "passive"))
      (node (ref "C92") (pin "2") (pinfunction "2_2") (pintype "passive"))
      (node (ref "C93") (pin "2") (pinfunction "2_2") (pintype "passive"))
      (node (ref "GND") (pin "TP") (pinfunction "TP_TP") (pintype "input"))
      (node (ref "GND75") (pin "TP") (pinfunction "TP_TP") (pintype "input"))
      (node (ref "GND77") (pin "TP") (pinfunction "TP_TP") (pintype "input"))
      (node (ref "R12") (pin "2") (pinfunction "2_2") (pintype "passive"))
      (node (ref "R15") (pin "2") (pinfunction "2_2") (pintype "passive"))
      (node (ref "R18") (pin "2") (pinfunction "2_2") (pintype "passive"))
      (node (ref "R22") (pin "1") (pinfunction "1_1") (pintype "passive"))
      (node (ref "R2X") (pin "2") (pinfunction "2_2") (pintype "passive"))
      (node (ref "R3") (pin "2") (pinfunction "2_2") (pintype "passive"))
      (node (ref "R6") (pin "2") (pinfunction "2_2") (pintype "passive"))
      (node (ref "R9") (pin "2") (pinfunction "2_2") (pintype "passive"))
      (node (ref "SENSOR") (pin "A21") (pinfunction "GND_A21") (pintype "power_in"))
      (node (ref "SENSOR") (pin "A25") (pinfunction "GND_A25") (pintype "power_in"))
      (node (ref "SENSOR") (pin "A28") (pinfunction "GND_A28") (pintype "power_in"))
      (node (ref "SENSOR") (pin "A29") (pinfunction "GND_A29") (pintype "power_in"))
      (node (ref "SENSOR") (pin "A9") (pinfunction "GND_A9") (pintype "power_in"))
      (node (ref "SENSOR") (pin "B22") (pinfunction "GND_B22") (pintype "power_in"))
      (node (ref "SENSOR") (pin "B26") (pinfunction "GND_B26") (pintype "power_in"))
      (node (ref "SENSOR") (pin "B27") (pinfunction "GND_B27") (pintype "power_in"))
      (node (ref "SENSOR") (pin "B28") (pinfunction "GND_B28") (pintype "power_in"))
      (node (ref "SENSOR") (pin "B5") (pinfunction "GND_B5") (pintype "power_in"))
      (node (ref "SENSOR") (pin "C15") (pinfunction "GND_C15") (pintype "power_in"))
      (node (ref "SENSOR") (pin "C16") (pinfunction "GND_C16") (pintype "power_in"))
      (node (ref "SENSOR") (pin "C28") (pinfunction "GND_C28") (pintype "power_in"))
      (node (ref "SENSOR") (pin "D2") (pinfunction "GND_D2") (pintype "power_in"))
      (node (ref "SENSOR") (pin "D25") (pinfunction "GND_D25") (pintype "power_in"))
      (node (ref "SENSOR") (pin "D27") (pinfunction "GND_D27") (pintype "power_in"))
      (node (ref "SENSOR") (pin "D29") (pinfunction "GND_D29") (pintype "power_in"))
      (node (ref "SENSOR") (pin "E15") (pinfunction "GND_E15") (pintype "power_in"))
      (node (ref "SENSOR") (pin "E16") (pinfunction "GND_E16") (pintype "power_in"))
      (node (ref "SENSOR") (pin "E25") (pinfunction "GND_E25") (pintype "power_in"))
      (node (ref "SENSOR") (pin "E27") (pinfunction "GND_E27") (pintype "power_in"))
      (node (ref "SENSOR") (pin "E3") (pinfunction "GND_E3") (pintype "power_in"))
      (node (ref "SENSOR") (pin "E4") (pinfunction "DIO2_E4") (pintype "output"))
      (node (ref "SENSOR") (pin "F27") (pinfunction "GND_F27") (pintype "power_in"))
      (node (ref "SENSOR") (pin "F4") (pinfunction "DIO1_F4") (pintype "output"))
      (node (ref "SENSOR") (pin "G3") (pinfunction "DIO4_G3") (pintype "output"))
      (node (ref "SENSOR") (pin "G5") (pinfunction "GND_G5") (pintype "power_in"))
      (node (ref "SENSOR") (pin "H1") (pinfunction "GND_H1") (pintype "power_in"))
      (node (ref "SENSOR") (pin "H21") (pinfunction "GND_H21") (pintype "power_in"))
      (node (ref "SENSOR") (pin "H25") (pinfunction "GND_H25") (pintype "power_in"))
      (node (ref "SENSOR") (pin "H27") (pinfunction "GND_H27") (pintype "power_in"))
      (node (ref "SENSOR") (pin "H4") (pinfunction "DIO3_H4") (pintype "output"))
      (node (ref "SENSOR") (pin "H6") (pinfunction "GND_H6") (pintype "power_in"))
      (node (ref "SENSOR") (pin "H9") (pinfunction "GND_H9") (pintype "power_in"))
      (node (ref "U1") (pin "6") (pinfunction "ANODE_6") (pintype "input"))
      (node (ref "U2") (pin "6") (pinfunction "ANODE_6") (pintype "input"))
      (node (ref "U3") (pin "2") (pinfunction "GND_2") (pintype "power_in"))
      (node (ref "U3") (pin "EP") (pinfunction "EP_EP") (pintype "power_in"))
      (node (ref "U4") (pin "16") (pinfunction "DIR2_16") (pintype "input"))
      (node (ref "U4") (pin "7") (pinfunction "~{OE}_7") (pintype "input"))
      (node (ref "U4") (pin "8") (pinfunction "GND_8") (pintype "passive"))
      (node (ref "U5") (pin "6") (pinfunction "DIR4_6") (pintype "input"))
      (node (ref "U5") (pin "7") (pinfunction "~{OE}_7") (pintype "input"))
      (node (ref "U5") (pin "8") (pinfunction "GND_8") (pintype "passive"))
      (node (ref "U6") (pin "16") (pinfunction "DIR2_16") (pintype "input"))
      (node (ref "U6") (pin "7") (pinfunction "~{OE}_7") (pintype "input"))
      (node (ref "U6") (pin "8") (pinfunction "GND_8") (pintype "passive"))
      (node (ref "U7") (pin "4") (pinfunction "GND_4") (pintype "power_in"))
      (node (ref "U7") (pin "5") (pinfunction "A2_5") (pintype "input"))
      (node (ref "U7") (pin "6") (pinfunction "A1_6") (pintype "input"))
      (node (ref "U7") (pin "7") (pinfunction "A0_7") (pintype "input"))
      (node (ref "UEP") (pin "1") (pinfunction "A0_1") (pintype "input"))
      (node (ref "UEP") (pin "2") (pinfunction "A1_2") (pintype "input"))
      (node (ref "UEP") (pin "3") (pinfunction "A2_3") (pintype "input"))
      (node (ref "UEP") (pin "4") (pinfunction "GND_4") (pintype "passive"))
      (node (ref "UEP") (pin "EP") (pinfunction "EP_EP") (pintype "passive"))
      (node (ref "UNE") (pin "4") (pinfunction "VSS_4") (pintype "power_in"))
      (node (ref "UNE") (pin "EP") (pinfunction "EP_EP") (pintype "passive"))
      (node (ref "UNN") (pin "4") (pinfunction "VSS_4") (pintype "power_in"))
      (node (ref "UNN") (pin "EP") (pinfunction "EP_EP") (pintype "passive"))
      (node (ref "UNW") (pin "4") (pinfunction "VSS_4") (pintype "power_in"))
      (node (ref "UNW") (pin "EP") (pinfunction "EP_EP") (pintype "passive"))
      (node (ref "USE") (pin "4") (pinfunction "VSS_4") (pintype "power_in"))
      (node (ref "USE") (pin "EP") (pinfunction "EP_EP") (pintype "passive"))
      (node (ref "USS") (pin "4") (pinfunction "VSS_4") (pintype "power_in"))
      (node (ref "USS") (pin "EP") (pinfunction "EP_EP") (pintype "passive"))
      (node (ref "USW") (pin "4") (pinfunction "VSS_4") (pintype "power_in"))
      (node (ref "USW") (pin "EP") (pinfunction "EP_EP") (pintype "passive"))
      (node (ref "X-NORTH") (pin "102") (pinfunction "102_102") (pintype "bidirectional"))
      (node (ref "X-NORTH") (pin "103") (pinfunction "103_103") (pintype "bidirectional"))
      (node (ref "X-NORTH") (pin "108") (pinfunction "108_108") (pintype "bidirectional"))
      (node (ref "X-NORTH") (pin "114") (pinfunction "114_114") (pintype "bidirectional"))
      (node (ref "X-NORTH") (pin "12") (pinfunction "12_12") (pintype "bidirectional"))
      (node (ref "X-NORTH") (pin "120") (pinfunction "120_120") (pintype "bidirectional"))
      (node (ref "X-NORTH") (pin "126") (pinfunction "126_126") (pintype "bidirectional"))
      (node (ref "X-NORTH") (pin "132") (pinfunction "132_132") (pintype "bidirectional"))
      (node (ref "X-NORTH") (pin "138") (pinfunction "138_138") (pintype "bidirectional"))
      (node (ref "X-NORTH") (pin "139") (pinfunction "139_139") (pintype "bidirectional"))
      (node (ref "X-NORTH") (pin "18") (pinfunction "18_18") (pintype "bidirectional"))
      (node (ref "X-NORTH") (pin "24") (pinfunction "24_24") (pintype "bidirectional"))
      (node (ref "X-NORTH") (pin "30") (pinfunction "30_30") (pintype "bidirectional"))
      (node (ref "X-NORTH") (pin "36") (pinfunction "36_36") (pintype "bidirectional"))
      (node (ref "X-NORTH") (pin "42") (pinfunction "42_42") (pintype "bidirectional"))
      (node (ref "X-NORTH") (pin "43") (pinfunction "43_43") (pintype "bidirectional"))
      (node (ref "X-NORTH") (pin "48") (pinfunction "48_48") (pintype "bidirectional"))
      (node (ref "X-NORTH") (pin "54") (pinfunction "54_54") (pintype "bidirectional"))
      (node (ref "X-NORTH") (pin "60") (pinfunction "60_60") (pintype "bidirectional"))
      (node (ref "X-NORTH") (pin "66") (pinfunction "66_66") (pintype "bidirectional"))
      (node (ref "X-NORTH") (pin "72") (pinfunction "72_72") (pintype "bidirectional"))
      (node (ref "X-NORTH") (pin "78") (pinfunction "78_78") (pintype "bidirectional"))
      (node (ref "X-NORTH") (pin "84") (pinfunction "84_84") (pintype "bidirectional"))
      (node (ref "X-NORTH") (pin "90") (pinfunction "90_90") (pintype "bidirectional"))
      (node (ref "X-NORTH") (pin "96") (pinfunction "96_96") (pintype "bidirectional"))
      (node (ref "X-SOUTH") (pin "102") (pinfunction "102_102") (pintype "bidirectional"))
      (node (ref "X-SOUTH") (pin "103") (pinfunction "103_103") (pintype "bidirectional"))
      (node (ref "X-SOUTH") (pin "108") (pinfunction "108_108") (pintype "bidirectional"))
      (node (ref "X-SOUTH") (pin "114") (pinfunction "114_114") (pintype "bidirectional"))
      (node (ref "X-SOUTH") (pin "12") (pinfunction "12_12") (pintype "bidirectional"))
      (node (ref "X-SOUTH") (pin "120") (pinfunction "120_120") (pintype "bidirectional"))
      (node (ref "X-SOUTH") (pin "126") (pinfunction "126_126") (pintype "bidirectional"))
      (node (ref "X-SOUTH") (pin "132") (pinfunction "132_132") (pintype "bidirectional"))
      (node (ref "X-SOUTH") (pin "138") (pinfunction "138_138") (pintype "bidirectional"))
      (node (ref "X-SOUTH") (pin "139") (pinfunction "139_139") (pintype "bidirectional"))
      (node (ref "X-SOUTH") (pin "18") (pinfunction "18_18") (pintype "bidirectional"))
      (node (ref "X-SOUTH") (pin "24") (pinfunction "24_24") (pintype "bidirectional"))
      (node (ref "X-SOUTH") (pin "30") (pinfunction "30_30") (pintype "bidirectional"))
      (node (ref "X-SOUTH") (pin "36") (pinfunction "36_36") (pintype "bidirectional"))
      (node (ref "X-SOUTH") (pin "42") (pinfunction "42_42") (pintype "bidirectional"))
      (node (ref "X-SOUTH") (pin "43") (pinfunction "43_43") (pintype "bidirectional"))
      (node (ref "X-SOUTH") (pin "48") (pinfunction "48_48") (pintype "bidirectional"))
      (node (ref "X-SOUTH") (pin "54") (pinfunction "54_54") (pintype "bidirectional"))
      (node (ref "X-SOUTH") (pin "60") (pinfunction "60_60") (pintype "bidirectional"))
      (node (ref "X-SOUTH") (pin "66") (pinfunction "66_66") (pintype "bidirectional"))
      (node (ref "X-SOUTH") (pin "72") (pinfunction "72_72") (pintype "bidirectional"))
      (node (ref "X-SOUTH") (pin "78") (pinfunction "78_78") (pintype "bidirectional"))
      (node (ref "X-SOUTH") (pin "84") (pinfunction "84_84") (pintype "bidirectional"))
      (node (ref "X-SOUTH") (pin "90") (pinfunction "90_90") (pintype "bidirectional"))
      (node (ref "X-SOUTH") (pin "96") (pinfunction "96_96") (pintype "bidirectional"))
    )
    (net (code "4") (name "N$42") (class "Default")
      (node (ref "SENSOR") (pin "A2") (pinfunction "TANA_A2") (pintype "output"))
    )
    (net (code "5") (name "N00_N") (class "Default")
      (node (ref "R25") (pin "2") (pinfunction "2_2") (pintype "passive"))
      (node (ref "SENSOR") (pin "E6") (pinfunction "LVDS_CLK_P_E6") (pintype "input"))
      (node (ref "X-NORTH") (pin "16") (pinfunction "16_16") (pintype "bidirectional"))
    )
    (net (code "6") (name "N00_P") (class "Default")
      (node (ref "R25") (pin "1") (pinfunction "1_1") (pintype "passive"))
      (node (ref "SENSOR") (pin "E5") (pinfunction "LVDS_CLK_N_E5") (pintype "input"))
      (node (ref "X-NORTH") (pin "14") (pinfunction "14_14") (pintype "bidirectional"))
    )
    (net (code "7") (name "N01_N") (class "Default")
      (node (ref "SENSOR") (pin "G7") (pinfunction "OUTCLK_P_G7") (pintype "output"))
      (node (ref "X-NORTH") (pin "17") (pinfunction "17_17") (pintype "bidirectional"))
    )
    (net (code "8") (name "N01_P") (class "Default")
      (node (ref "SENSOR") (pin "G6") (pinfunction "OUTCLK_N_G6") (pintype "output"))
      (node (ref "X-NORTH") (pin "15") (pinfunction "15_15") (pintype "bidirectional"))
    )
    (net (code "9") (name "N02_N") (class "Default")
      (node (ref "SENSOR") (pin "F7") (pinfunction "OUT33_P_F7") (pintype "output"))
      (node (ref "X-NORTH") (pin "22") (pinfunction "22_22") (pintype "bidirectional"))
    )
    (net (code "10") (name "N02_P") (class "Default")
      (node (ref "SENSOR") (pin "F6") (pinfunction "OUT33_N_F6") (pintype "output"))
      (node (ref "X-NORTH") (pin "20") (pinfunction "20_20") (pintype "bidirectional"))
    )
    (net (code "11") (name "N03_N") (class "Default")
      (node (ref "X-NORTH") (pin "23") (pinfunction "23_23") (pintype "bidirectional"))
    )
    (net (code "12") (name "N03_P") (class "Default")
      (node (ref "X-NORTH") (pin "21") (pinfunction "21_21") (pintype "bidirectional"))
    )
    (net (code "13") (name "N04_N") (class "Default")
      (node (ref "SENSOR") (pin "E8") (pinfunction "OUT35_P_E8") (pintype "output"))
      (node (ref "X-NORTH") (pin "28") (pinfunction "28_28") (pintype "bidirectional"))
    )
    (net (code "14") (name "N04_P") (class "Default")
      (node (ref "SENSOR") (pin "E7") (pinfunction "OUT35_N_E7") (pintype "output"))
      (node (ref "X-NORTH") (pin "26") (pinfunction "26_26") (pintype "bidirectional"))
    )
    (net (code "15") (name "N05_N") (class "Default")
      (node (ref "SENSOR") (pin "H8") (pinfunction "OUT34_P_H8") (pintype "output"))
      (node (ref "X-NORTH") (pin "29") (pinfunction "29_29") (pintype "bidirectional"))
    )
    (net (code "16") (name "N05_P") (class "Default")
      (node (ref "SENSOR") (pin "H7") (pinfunction "OUT34_N_H7") (pintype "output"))
      (node (ref "X-NORTH") (pin "27") (pinfunction "27_27") (pintype "bidirectional"))
    )
    (net (code "17") (name "N06_N") (class "Default")
      (node (ref "SENSOR") (pin "F9") (pinfunction "OUT37_P_F9") (pintype "output"))
      (node (ref "X-NORTH") (pin "34") (pinfunction "34_34") (pintype "bidirectional"))
    )
    (net (code "18") (name "N06_P") (class "Default")
      (node (ref "SENSOR") (pin "F8") (pinfunction "OUT37_N_F8") (pintype "output"))
      (node (ref "X-NORTH") (pin "32") (pinfunction "32_32") (pintype "bidirectional"))
    )
    (net (code "19") (name "N07_N") (class "Default")
      (node (ref "SENSOR") (pin "G9") (pinfunction "OUT36_P_G9") (pintype "output"))
      (node (ref "X-NORTH") (pin "35") (pinfunction "35_35") (pintype "bidirectional"))
    )
    (net (code "20") (name "N07_P") (class "Default")
      (node (ref "SENSOR") (pin "G8") (pinfunction "OUT36_N_G8") (pintype "output"))
      (node (ref "X-NORTH") (pin "33") (pinfunction "33_33") (pintype "bidirectional"))
    )
    (net (code "21") (name "N08_N") (class "Default")
      (node (ref "SENSOR") (pin "E10") (pinfunction "OUT38_P_E10") (pintype "output"))
      (node (ref "X-NORTH") (pin "40") (pinfunction "40_40") (pintype "bidirectional"))
    )
    (net (code "22") (name "N08_P") (class "Default")
      (node (ref "SENSOR") (pin "E9") (pinfunction "OUT38_N_E9") (pintype "output"))
      (node (ref "X-NORTH") (pin "38") (pinfunction "38_38") (pintype "bidirectional"))
    )
    (net (code "23") (name "N09_N") (class "Default")
      (node (ref "SENSOR") (pin "G11") (pinfunction "OUT39_P_G11") (pintype "output"))
      (node (ref "X-NORTH") (pin "41") (pinfunction "41_41") (pintype "bidirectional"))
    )
    (net (code "24") (name "N09_P") (class "Default")
      (node (ref "SENSOR") (pin "G10") (pinfunction "OUT39_N_G10") (pintype "output"))
      (node (ref "X-NORTH") (pin "39") (pinfunction "39_39") (pintype "bidirectional"))
    )
    (net (code "25") (name "N10_N") (class "Default")
      (node (ref "SENSOR") (pin "F11") (pinfunction "OUT40_P_F11") (pintype "output"))
      (node (ref "X-NORTH") (pin "46") (pinfunction "46_46") (pintype "bidirectional"))
    )
    (net (code "26") (name "N10_P") (class "Default")
      (node (ref "SENSOR") (pin "F10") (pinfunction "OUT40_N_F10") (pintype "output"))
      (node (ref "X-NORTH") (pin "44") (pinfunction "44_44") (pintype "bidirectional"))
    )
    (net (code "27") (name "N11_N") (class "Default")
      (node (ref "SENSOR") (pin "H12") (pinfunction "OUT41_P_H12") (pintype "output"))
      (node (ref "X-NORTH") (pin "47") (pinfunction "47_47") (pintype "bidirectional"))
    )
    (net (code "28") (name "N11_P") (class "Default")
      (node (ref "SENSOR") (pin "H11") (pinfunction "OUT41_N_H11") (pintype "output"))
      (node (ref "X-NORTH") (pin "45") (pinfunction "45_45") (pintype "bidirectional"))
    )
    (net (code "29") (name "N12_N") (class "Default")
      (node (ref "SENSOR") (pin "E12") (pinfunction "OUT42_P_E12") (pintype "output"))
      (node (ref "X-NORTH") (pin "52") (pinfunction "52_52") (pintype "bidirectional"))
    )
    (net (code "30") (name "N12_P") (class "Default")
      (node (ref "SENSOR") (pin "E11") (pinfunction "OUT42_N_E11") (pintype "output"))
      (node (ref "X-NORTH") (pin "50") (pinfunction "50_50") (pintype "bidirectional"))
    )
    (net (code "31") (name "N13_N") (class "Default")
      (node (ref "SENSOR") (pin "G13") (pinfunction "OUT43_P_G13") (pintype "output"))
      (node (ref "X-NORTH") (pin "53") (pinfunction "53_53") (pintype "bidirectional"))
    )
    (net (code "32") (name "N13_P") (class "Default")
      (node (ref "SENSOR") (pin "G12") (pinfunction "OUT43_N_G12") (pintype "output"))
      (node (ref "X-NORTH") (pin "51") (pinfunction "51_51") (pintype "bidirectional"))
    )
    (net (code "33") (name "N14_N") (class "Default")
      (node (ref "SENSOR") (pin "F13") (pinfunction "OUT44_P_F13") (pintype "output"))
      (node (ref "X-NORTH") (pin "58") (pinfunction "58_58") (pintype "bidirectional"))
    )
    (net (code "34") (name "N14_P") (class "Default")
      (node (ref "SENSOR") (pin "F12") (pinfunction "OUT44_N_F12") (pintype "output"))
      (node (ref "X-NORTH") (pin "56") (pinfunction "56_56") (pintype "bidirectional"))
    )
    (net (code "35") (name "N15_N") (class "Default")
      (node (ref "SENSOR") (pin "H14") (pinfunction "OUT45_P_H14") (pintype "output"))
      (node (ref "X-NORTH") (pin "59") (pinfunction "59_59") (pintype "bidirectional"))
    )
    (net (code "36") (name "N15_P") (class "Default")
      (node (ref "SENSOR") (pin "H13") (pinfunction "OUT45_N_H13") (pintype "output"))
      (node (ref "X-NORTH") (pin "57") (pinfunction "57_57") (pintype "bidirectional"))
    )
    (net (code "37") (name "N16_N") (class "Default")
      (node (ref "SENSOR") (pin "E14") (pinfunction "OUT46_P_E14") (pintype "output"))
      (node (ref "X-NORTH") (pin "64") (pinfunction "64_64") (pintype "bidirectional"))
    )
    (net (code "38") (name "N16_P") (class "Default")
      (node (ref "SENSOR") (pin "E13") (pinfunction "OUT46_N_E13") (pintype "output"))
      (node (ref "X-NORTH") (pin "62") (pinfunction "62_62") (pintype "bidirectional"))
    )
    (net (code "39") (name "N17_N") (class "Default")
      (node (ref "SENSOR") (pin "G15") (pinfunction "OUT47_P_G15") (pintype "output"))
      (node (ref "X-NORTH") (pin "65") (pinfunction "65_65") (pintype "bidirectional"))
    )
    (net (code "40") (name "N17_P") (class "Default")
      (node (ref "SENSOR") (pin "G14") (pinfunction "OUT47_N_G14") (pintype "output"))
      (node (ref "X-NORTH") (pin "63") (pinfunction "63_63") (pintype "bidirectional"))
    )
    (net (code "41") (name "N18_N") (class "Default")
      (node (ref "SENSOR") (pin "F15") (pinfunction "OUT48_P_F15") (pintype "output"))
      (node (ref "X-NORTH") (pin "70") (pinfunction "70_70") (pintype "bidirectional"))
    )
    (net (code "42") (name "N18_P") (class "Default")
      (node (ref "SENSOR") (pin "F14") (pinfunction "OUT48_N_F14") (pintype "output"))
      (node (ref "X-NORTH") (pin "68") (pinfunction "68_68") (pintype "bidirectional"))
    )
    (net (code "43") (name "N19_N") (class "Default")
      (node (ref "SENSOR") (pin "G17") (pinfunction "OUT50_P_G17") (pintype "output"))
      (node (ref "X-NORTH") (pin "71") (pinfunction "71_71") (pintype "bidirectional"))
    )
    (net (code "44") (name "N19_P") (class "Default")
      (node (ref "SENSOR") (pin "G16") (pinfunction "OUT50_N_G16") (pintype "output"))
      (node (ref "X-NORTH") (pin "69") (pinfunction "69_69") (pintype "bidirectional"))
    )
    (net (code "45") (name "N20_N") (class "Default")
      (node (ref "SENSOR") (pin "F17") (pinfunction "OUT49_P_F17") (pintype "output"))
      (node (ref "X-NORTH") (pin "76") (pinfunction "76_76") (pintype "bidirectional"))
    )
    (net (code "46") (name "N20_P") (class "Default")
      (node (ref "SENSOR") (pin "F16") (pinfunction "OUT49_N_F16") (pintype "output"))
      (node (ref "X-NORTH") (pin "74") (pinfunction "74_74") (pintype "bidirectional"))
    )
    (net (code "47") (name "N21_N") (class "Default")
      (node (ref "SENSOR") (pin "H18") (pinfunction "OUT52_P_H18") (pintype "output"))
      (node (ref "X-NORTH") (pin "77") (pinfunction "77_77") (pintype "bidirectional"))
    )
    (net (code "48") (name "N21_P") (class "Default")
      (node (ref "SENSOR") (pin "H17") (pinfunction "OUT52_N_H17") (pintype "output"))
      (node (ref "X-NORTH") (pin "75") (pinfunction "75_75") (pintype "bidirectional"))
    )
    (net (code "49") (name "N22_N") (class "Default")
      (node (ref "SENSOR") (pin "E18") (pinfunction "OUT51_P_E18") (pintype "output"))
      (node (ref "X-NORTH") (pin "82") (pinfunction "82_82") (pintype "bidirectional"))
    )
    (net (code "50") (name "N22_P") (class "Default")
      (node (ref "SENSOR") (pin "E17") (pinfunction "OUT51_N_E17") (pintype "output"))
      (node (ref "X-NORTH") (pin "80") (pinfunction "80_80") (pintype "bidirectional"))
    )
    (net (code "51") (name "N23_N") (class "Default")
      (node (ref "SENSOR") (pin "G19") (pinfunction "OUT54_P_G19") (pintype "output"))
      (node (ref "X-NORTH") (pin "83") (pinfunction "83_83") (pintype "bidirectional"))
    )
    (net (code "52") (name "N23_P") (class "Default")
      (node (ref "SENSOR") (pin "G18") (pinfunction "OUT54_N_G18") (pintype "output"))
      (node (ref "X-NORTH") (pin "81") (pinfunction "81_81") (pintype "bidirectional"))
    )
    (net (code "53") (name "N24_N") (class "Default")
      (node (ref "SENSOR") (pin "F19") (pinfunction "OUT53_P_F19") (pintype "output"))
      (node (ref "X-NORTH") (pin "88") (pinfunction "88_88") (pintype "bidirectional"))
    )
    (net (code "54") (name "N24_P") (class "Default")
      (node (ref "SENSOR") (pin "F18") (pinfunction "OUT53_N_F18") (pintype "output"))
      (node (ref "X-NORTH") (pin "86") (pinfunction "86_86") (pintype "bidirectional"))
    )
    (net (code "55") (name "N25_N") (class "Default")
      (node (ref "SENSOR") (pin "H20") (pinfunction "OUT56_P_H20") (pintype "output"))
      (node (ref "X-NORTH") (pin "89") (pinfunction "89_89") (pintype "bidirectional"))
    )
    (net (code "56") (name "N25_P") (class "Default")
      (node (ref "SENSOR") (pin "H19") (pinfunction "OUT56_N_H19") (pintype "output"))
      (node (ref "X-NORTH") (pin "87") (pinfunction "87_87") (pintype "bidirectional"))
    )
    (net (code "57") (name "N26_N") (class "Default")
      (node (ref "SENSOR") (pin "E20") (pinfunction "OUT55_P_E20") (pintype "output"))
      (node (ref "X-NORTH") (pin "94") (pinfunction "94_94") (pintype "bidirectional"))
    )
    (net (code "58") (name "N26_P") (class "Default")
      (node (ref "SENSOR") (pin "E19") (pinfunction "OUT55_N_E19") (pintype "output"))
      (node (ref "X-NORTH") (pin "92") (pinfunction "92_92") (pintype "bidirectional"))
    )
    (net (code "59") (name "N27_N") (class "Default")
      (node (ref "SENSOR") (pin "G21") (pinfunction "OUT58_P_G21") (pintype "output"))
      (node (ref "X-NORTH") (pin "95") (pinfunction "95_95") (pintype "bidirectional"))
    )
    (net (code "60") (name "N27_P") (class "Default")
      (node (ref "SENSOR") (pin "G20") (pinfunction "OUT58_N_G20") (pintype "output"))
      (node (ref "X-NORTH") (pin "93") (pinfunction "93_93") (pintype "bidirectional"))
    )
    (net (code "61") (name "N28_N") (class "Default")
      (node (ref "SENSOR") (pin "F21") (pinfunction "OUT57_P_F21") (pintype "output"))
      (node (ref "X-NORTH") (pin "100") (pinfunction "100_100") (pintype "bidirectional"))
    )
    (net (code "62") (name "N28_P") (class "Default")
      (node (ref "SENSOR") (pin "F20") (pinfunction "OUT57_N_F20") (pintype "output"))
      (node (ref "X-NORTH") (pin "98") (pinfunction "98_98") (pintype "bidirectional"))
    )
    (net (code "63") (name "N29_N") (class "Default")
      (node (ref "SENSOR") (pin "G23") (pinfunction "OUT61_P_G23") (pintype "output"))
      (node (ref "X-NORTH") (pin "101") (pinfunction "101_101") (pintype "bidirectional"))
    )
    (net (code "64") (name "N29_P") (class "Default")
      (node (ref "SENSOR") (pin "G22") (pinfunction "OUT61_N_G22") (pintype "output"))
      (node (ref "X-NORTH") (pin "99") (pinfunction "99_99") (pintype "bidirectional"))
    )
    (net (code "65") (name "N30_N") (class "Default")
      (node (ref "SENSOR") (pin "E22") (pinfunction "OUT59_P_E22") (pintype "output"))
      (node (ref "X-NORTH") (pin "106") (pinfunction "106_106") (pintype "bidirectional"))
    )
    (net (code "66") (name "N30_P") (class "Default")
      (node (ref "SENSOR") (pin "E21") (pinfunction "OUT59_N_E21") (pintype "output"))
      (node (ref "X-NORTH") (pin "104") (pinfunction "104_104") (pintype "bidirectional"))
    )
    (net (code "67") (name "N31_N") (class "Default")
      (node (ref "SENSOR") (pin "H24") (pinfunction "OUT63_P_H24") (pintype "output"))
      (node (ref "X-NORTH") (pin "107") (pinfunction "107_107") (pintype "bidirectional"))
    )
    (net (code "68") (name "N31_P") (class "Default")
      (node (ref "SENSOR") (pin "H23") (pinfunction "OUT63_N_H23") (pintype "output"))
      (node (ref "X-NORTH") (pin "105") (pinfunction "105_105") (pintype "bidirectional"))
    )
    (net (code "69") (name "N32_N") (class "Default")
      (node (ref "SENSOR") (pin "F23") (pinfunction "OUT60_P_F23") (pintype "output"))
      (node (ref "X-NORTH") (pin "112") (pinfunction "112_112") (pintype "bidirectional"))
    )
    (net (code "70") (name "N32_P") (class "Default")
      (node (ref "SENSOR") (pin "F22") (pinfunction "OUT60_N_F22") (pintype "output"))
      (node (ref "X-NORTH") (pin "110") (pinfunction "110_110") (pintype "bidirectional"))
    )
    (net (code "71") (name "N33_N") (class "Default")
      (node (ref "SENSOR") (pin "G25") (pinfunction "OUT64_P_G25") (pintype "output"))
      (node (ref "X-NORTH") (pin "113") (pinfunction "113_113") (pintype "bidirectional"))
    )
    (net (code "72") (name "N33_P") (class "Default")
      (node (ref "SENSOR") (pin "G24") (pinfunction "OUT64_N_G24") (pintype "output"))
      (node (ref "X-NORTH") (pin "111") (pinfunction "111_111") (pintype "bidirectional"))
    )
    (net (code "73") (name "N34_N") (class "Default")
      (node (ref "SENSOR") (pin "E24") (pinfunction "OUT62_P_E24") (pintype "output"))
      (node (ref "X-NORTH") (pin "118") (pinfunction "118_118") (pintype "bidirectional"))
    )
    (net (code "74") (name "N34_P") (class "Default")
      (node (ref "SENSOR") (pin "E23") (pinfunction "OUT62_N_E23") (pintype "output"))
      (node (ref "X-NORTH") (pin "116") (pinfunction "116_116") (pintype "bidirectional"))
    )
    (net (code "75") (name "N35_N") (class "Default")
      (node (ref "U6") (pin "4") (pinfunction "A4_4") (pintype "bidirectional"))
      (node (ref "X-NORTH") (pin "119") (pinfunction "119_119") (pintype "bidirectional"))
    )
    (net (code "76") (name "N35_P") (class "Default")
      (node (ref "U6") (pin "3") (pinfunction "A3_3") (pintype "bidirectional"))
      (node (ref "X-NORTH") (pin "117") (pinfunction "117_117") (pintype "bidirectional"))
    )
    (net (code "77") (name "N36_N") (class "Default")
      (node (ref "X-NORTH") (pin "124") (pinfunction "124_124") (pintype "bidirectional"))
    )
    (net (code "78") (name "N36_P") (class "Default")
      (node (ref "X-NORTH") (pin "122") (pinfunction "122_122") (pintype "bidirectional"))
    )
    (net (code "79") (name "N37_N") (class "Default")
      (node (ref "U5") (pin "3") (pinfunction "A3_3") (pintype "bidirectional"))
      (node (ref "X-NORTH") (pin "125") (pinfunction "125_125") (pintype "bidirectional"))
    )
    (net (code "80") (name "N37_P") (class "Default")
      (node (ref "U5") (pin "4") (pinfunction "A4_4") (pintype "bidirectional"))
      (node (ref "X-NORTH") (pin "123") (pinfunction "123_123") (pintype "bidirectional"))
    )
    (net (code "81") (name "N38_N") (class "Default")
      (node (ref "U6") (pin "2") (pinfunction "A2_2") (pintype "bidirectional"))
      (node (ref "X-NORTH") (pin "130") (pinfunction "130_130") (pintype "bidirectional"))
    )
    (net (code "82") (name "N38_P") (class "Default")
      (node (ref "U6") (pin "1") (pinfunction "A1_1") (pintype "bidirectional"))
      (node (ref "X-NORTH") (pin "128") (pinfunction "128_128") (pintype "bidirectional"))
    )
    (net (code "83") (name "N39_N") (class "Default")
      (node (ref "U5") (pin "1") (pinfunction "A1_1") (pintype "bidirectional"))
      (node (ref "X-NORTH") (pin "131") (pinfunction "131_131") (pintype "bidirectional"))
    )
    (net (code "84") (name "N39_P") (class "Default")
      (node (ref "U5") (pin "2") (pinfunction "A2_2") (pintype "bidirectional"))
      (node (ref "X-NORTH") (pin "129") (pinfunction "129_129") (pintype "bidirectional"))
    )
    (net (code "85") (name "N_CHK_EN") (class "Default")
      (node (ref "X-NORTH") (pin "8") (pinfunction "8_8") (pintype "bidirectional"))
    )
    (net (code "86") (name "N_CHK_V") (class "Default")
      (node (ref "C2") (pin "1") (pinfunction "1_1") (pintype "passive"))
      (node (ref "C3") (pin "1") (pinfunction "1_1") (pintype "passive"))
      (node (ref "C4") (pin "1") (pinfunction "1_1") (pintype "passive"))
      (node (ref "R19") (pin "1") (pinfunction "1_1") (pintype "passive"))
      (node (ref "TP1") (pin "TP") (pinfunction "TP_TP") (pintype "input"))
      (node (ref "UNE") (pin "8") (pinfunction "VDD_8") (pintype "power_in"))
      (node (ref "UNN") (pin "8") (pinfunction "VDD_8") (pintype "power_in"))
      (node (ref "UNW") (pin "8") (pinfunction "VDD_8") (pintype "power_in"))
      (node (ref "X-NORTH") (pin "10") (pinfunction "10_10") (pintype "bidirectional"))
    )
    (net (code "87") (name "N_I2C_EN") (class "Default")
      (node (ref "X-NORTH") (pin "137") (pinfunction "137_137") (pintype "bidirectional"))
    )
    (net (code "88") (name "N_I2C_V") (class "Default")
      (node (ref "C1") (pin "1") (pinfunction "1_1") (pintype "passive"))
      (node (ref "R1X") (pin "1") (pinfunction "1_1") (pintype "passive"))
      (node (ref "UEP") (pin "8") (pinfunction "VCC_8") (pintype "power_in"))
      (node (ref "X-NORTH") (pin "135") (pinfunction "135_135") (pintype "bidirectional"))
    )
    (net (code "89") (name "N_REF") (class "Default")
      (node (ref "R19") (pin "2") (pinfunction "2_2") (pintype "passive"))
      (node (ref "TP2") (pin "TP") (pinfunction "TP_TP") (pintype "input"))
      (node (ref "U1") (pin "1") (pinfunction "CATHODE_1") (pintype "output"))
      (node (ref "U1") (pin "3") (pinfunction "REF_3") (pintype "input"))
      (node (ref "UNE") (pin "2") (pinfunction "VINA-_2") (pintype "input"))
      (node (ref "UNE") (pin "5") (pinfunction "VINB+_5") (pintype "input"))
      (node (ref "UNN") (pin "2") (pinfunction "VINA-_2") (pintype "input"))
      (node (ref "UNN") (pin "5") (pinfunction "VINB+_5") (pintype "input"))
      (node (ref "UNW") (pin "2") (pinfunction "VINA-_2") (pintype "input"))
      (node (ref "UNW") (pin "5") (pinfunction "VINB+_5") (pintype "input"))
    )
    (net (code "90") (name "N_SCK") (class "Default")
      (node (ref "U4") (pin "4") (pinfunction "A4_4") (pintype "bidirectional"))
      (node (ref "X-NORTH") (pin "144") (pinfunction "144_144") (pintype "bidirectional"))
    )
    (net (code "91") (name "N_SCL") (class "Default")
      (node (ref "UEP") (pin "6") (pinfunction "SCL_6") (pintype "input"))
      (node (ref "X-NORTH") (pin "143") (pinfunction "143_143") (pintype "bidirectional"))
    )
    (net (code "92") (name "N_SDA") (class "Default")
      (node (ref "UEP") (pin "5") (pinfunction "SDA_5") (pintype "bidirectional"))
      (node (ref "X-NORTH") (pin "141") (pinfunction "141_141") (pintype "bidirectional"))
    )
    (net (code "93") (name "N_SDI") (class "Default")
      (node (ref "U4") (pin "2") (pinfunction "A2_2") (pintype "bidirectional"))
      (node (ref "X-NORTH") (pin "140") (pinfunction "140_140") (pintype "bidirectional"))
    )
    (net (code "94") (name "N_SDO") (class "Default")
      (node (ref "U4") (pin "3") (pinfunction "A3_3") (pintype "bidirectional"))
      (node (ref "X-NORTH") (pin "142") (pinfunction "142_142") (pintype "bidirectional"))
    )
    (net (code "95") (name "N_SPI_EN") (class "Default")
      (node (ref "U4") (pin "1") (pinfunction "A1_1") (pintype "bidirectional"))
      (node (ref "X-NORTH") (pin "136") (pinfunction "136_136") (pintype "bidirectional"))
    )
    (net (code "96") (name "N_SPI_V") (class "Default")
      (node (ref "C59") (pin "1") (pinfunction "1_1") (pintype "passive"))
      (node (ref "U4") (pin "14") (pinfunction "VCCA_14") (pintype "power_in"))
      (node (ref "U4") (pin "15") (pinfunction "DIR1_15") (pintype "input"))
      (node (ref "U4") (pin "5") (pinfunction "DIR3_5") (pintype "input"))
      (node (ref "U4") (pin "6") (pinfunction "DIR4_6") (pintype "input"))
      (node (ref "X-NORTH") (pin "134") (pinfunction "134_134") (pintype "bidirectional"))
    )
    (net (code "97") (name "N_VE") (class "Default")
      (node (ref "C50") (pin "1") (pinfunction "1_1") (pintype "passive"))
      (node (ref "C51") (pin "1") (pinfunction "1_1") (pintype "passive"))
      (node (ref "C52") (pin "1") (pinfunction "1_1") (pintype "passive"))
      (node (ref "C53") (pin "1") (pinfunction "1_1") (pintype "passive"))
      (node (ref "C54") (pin "1") (pinfunction "1_1") (pintype "passive"))
      (node (ref "C55") (pin "1") (pinfunction "1_1") (pintype "passive"))
      (node (ref "C56") (pin "1") (pinfunction "1_1") (pintype "passive"))
      (node (ref "C67") (pin "1") (pinfunction "1_1") (pintype "passive"))
      (node (ref "C69") (pin "1") (pinfunction "1_1") (pintype "passive"))
      (node (ref "C75") (pin "1") (pinfunction "1_1") (pintype "passive"))
      (node (ref "C76") (pin "1") (pinfunction "1_1") (pintype "passive"))
      (node (ref "C77") (pin "1") (pinfunction "1_1") (pintype "passive"))
      (node (ref "C84") (pin "1") (pinfunction "1_1") (pintype "passive"))
      (node (ref "C85") (pin "1") (pinfunction "1_1") (pintype "passive"))
      (node (ref "C86") (pin "1") (pinfunction "1_1") (pintype "passive"))
      (node (ref "C93") (pin "1") (pinfunction "1_1") (pintype "passive"))
      (node (ref "SENSOR") (pin "C26") (pinfunction "VDD33_C26") (pintype "power_in"))
      (node (ref "SENSOR") (pin "C27") (pinfunction "VDD33_C27") (pintype "power_in"))
      (node (ref "SENSOR") (pin "D26") (pinfunction "VDD33_D26") (pintype "power_in"))
      (node (ref "SENSOR") (pin "D3") (pinfunction "VDD33_D3") (pintype "power_in"))
      (node (ref "SENSOR") (pin "E26") (pinfunction "VDD33_E26") (pintype "power_in"))
      (node (ref "SENSOR") (pin "F26") (pinfunction "VDD33_F26") (pintype "power_in"))
      (node (ref "SENSOR") (pin "F5") (pinfunction "VDD33_F5") (pintype "power_in"))
      (node (ref "TP7") (pin "TP") (pinfunction "TP_TP") (pintype "input"))
      (node (ref "U4") (pin "13") (pinfunction "VCCB_13") (pintype "power_in"))
      (node (ref "U5") (pin "13") (pinfunction "VCCB_13") (pintype "power_in"))
      (node (ref "U6") (pin "13") (pinfunction "VCCB_13") (pintype "power_in"))
      (node (ref "X-NORTH") (pin "109") (pinfunction "109_109") (pintype "bidirectional"))
      (node (ref "X-NORTH") (pin "115") (pinfunction "115_115") (pintype "bidirectional"))
      (node (ref "X-NORTH") (pin "121") (pinfunction "121_121") (pintype "bidirectional"))
      (node (ref "X-NORTH") (pin "127") (pinfunction "127_127") (pintype "bidirectional"))
      (node (ref "X-NORTH") (pin "133") (pinfunction "133_133") (pintype "bidirectional"))
    )
    (net (code "98") (name "N_VE_CV") (class "Default")
      (node (ref "C10") (pin "1") (pinfunction "1_1") (pintype "passive"))
      (node (ref "R7") (pin "1") (pinfunction "1_1") (pintype "passive"))
      (node (ref "X-NORTH") (pin "6") (pinfunction "6_6") (pintype "bidirectional"))
    )
    (net (code "99") (name "N_VE_OV") (class "Default")
      (node (ref "UNE") (pin "7") (pinfunction "OUTB_7") (pintype "output"))
      (node (ref "X-NORTH") (pin "5") (pinfunction "5_5") (pintype "bidirectional"))
    )
    (net (code "100") (name "N_VE_UV") (class "Default")
      (node (ref "UNE") (pin "1") (pinfunction "OUTA_1") (pintype "output"))
      (node (ref "X-NORTH") (pin "11") (pinfunction "11_11") (pintype "bidirectional"))
    )
    (net (code "101") (name "N_VN") (class "Default")
      (node (ref "C31") (pin "1") (pinfunction "1_1") (pintype "passive"))
      (node (ref "C32") (pin "1") (pinfunction "1_1") (pintype "passive"))
      (node (ref "C33") (pin "1") (pinfunction "1_1") (pintype "passive"))
      (node (ref "C34") (pin "1") (pinfunction "1_1") (pintype "passive"))
      (node (ref "C35") (pin "1") (pinfunction "1_1") (pintype "passive"))
      (node (ref "C36") (pin "1") (pinfunction "1_1") (pintype "passive"))
      (node (ref "C37") (pin "1") (pinfunction "1_1") (pintype "passive"))
      (node (ref "C38") (pin "1") (pinfunction "1_1") (pintype "passive"))
      (node (ref "C39") (pin "1") (pinfunction "1_1") (pintype "passive"))
      (node (ref "C40") (pin "1") (pinfunction "1_1") (pintype "passive"))
      (node (ref "C41") (pin "1") (pinfunction "1_1") (pintype "passive"))
      (node (ref "C42") (pin "1") (pinfunction "1_1") (pintype "passive"))
      (node (ref "C43") (pin "1") (pinfunction "1_1") (pintype "passive"))
      (node (ref "C44") (pin "1") (pinfunction "1_1") (pintype "passive"))
      (node (ref "C68") (pin "1") (pinfunction "1_1") (pintype "passive"))
      (node (ref "C70") (pin "1") (pinfunction "1_1") (pintype "passive"))
      (node (ref "C78") (pin "1") (pinfunction "1_1") (pintype "passive"))
      (node (ref "C79") (pin "1") (pinfunction "1_1") (pintype "passive"))
      (node (ref "C80") (pin "1") (pinfunction "1_1") (pintype "passive"))
      (node (ref "C87") (pin "1") (pinfunction "1_1") (pintype "passive"))
      (node (ref "C88") (pin "1") (pinfunction "1_1") (pintype "passive"))
      (node (ref "C89") (pin "1") (pinfunction "1_1") (pintype "passive"))
      (node (ref "SENSOR") (pin "A10") (pinfunction "VDD18_A10") (pintype "power_in"))
      (node (ref "SENSOR") (pin "A15") (pinfunction "VDD18_A15") (pintype "power_in"))
      (node (ref "SENSOR") (pin "A16") (pinfunction "VDD18_A16") (pintype "power_in"))
      (node (ref "SENSOR") (pin "A22") (pinfunction "VDD18_A22") (pintype "power_in"))
      (node (ref "SENSOR") (pin "A26") (pinfunction "VDD18_A26") (pintype "power_in"))
      (node (ref "SENSOR") (pin "A27") (pinfunction "VDD18_A27") (pintype "power_in"))
      (node (ref "SENSOR") (pin "B4") (pinfunction "VDD18_B4") (pintype "power_in"))
      (node (ref "SENSOR") (pin "E1") (pinfunction "VDD18_PLL_E1") (pintype "power_in"))
      (node (ref "SENSOR") (pin "H10") (pinfunction "VDD18_H10") (pintype "power_in"))
      (node (ref "SENSOR") (pin "H15") (pinfunction "VDD18_H15") (pintype "power_in"))
      (node (ref "SENSOR") (pin "H16") (pinfunction "VDD18_H16") (pintype "power_in"))
      (node (ref "SENSOR") (pin "H22") (pinfunction "VDD18_H22") (pintype "power_in"))
      (node (ref "SENSOR") (pin "H26") (pinfunction "VDD18_H26") (pintype "power_in"))
      (node (ref "SENSOR") (pin "H5") (pinfunction "VDD18_H5") (pintype "power_in"))
      (node (ref "TP5") (pin "TP") (pinfunction "TP_TP") (pintype "input"))
      (node (ref "U5") (pin "14") (pinfunction "VCCA_14") (pintype "power_in"))
      (node (ref "U5") (pin "15") (pinfunction "DIR1_15") (pintype "input"))
      (node (ref "U5") (pin "16") (pinfunction "DIR2_16") (pintype "input"))
      (node (ref "U5") (pin "5") (pinfunction "DIR3_5") (pintype "input"))
      (node (ref "U6") (pin "14") (pinfunction "VCCA_14") (pintype "power_in"))
      (node (ref "U6") (pin "15") (pinfunction "DIR1_15") (pintype "input"))
      (node (ref "U6") (pin "5") (pinfunction "DIR3_5") (pintype "input"))
      (node (ref "U6") (pin "6") (pinfunction "DIR4_6") (pintype "input"))
      (node (ref "X-NORTH") (pin "49") (pinfunction "49_49") (pintype "bidirectional"))
      (node (ref "X-NORTH") (pin "55") (pinfunction "55_55") (pintype "bidirectional"))
      (node (ref "X-NORTH") (pin "61") (pinfunction "61_61") (pintype "bidirectional"))
      (node (ref "X-NORTH") (pin "67") (pinfunction "67_67") (pintype "bidirectional"))
      (node (ref "X-NORTH") (pin "73") (pinfunction "73_73") (pintype "bidirectional"))
      (node (ref "X-NORTH") (pin "79") (pinfunction "79_79") (pintype "bidirectional"))
      (node (ref "X-NORTH") (pin "85") (pinfunction "85_85") (pintype "bidirectional"))
      (node (ref "X-NORTH") (pin "91") (pinfunction "91_91") (pintype "bidirectional"))
      (node (ref "X-NORTH") (pin "97") (pinfunction "97_97") (pintype "bidirectional"))
    )
    (net (code "102") (name "N_VN_CV") (class "Default")
      (node (ref "C9") (pin "1") (pinfunction "1_1") (pintype "passive"))
      (node (ref "R4") (pin "1") (pinfunction "1_1") (pintype "passive"))
      (node (ref "X-NORTH") (pin "4") (pinfunction "4_4") (pintype "bidirectional"))
    )
    (net (code "103") (name "N_VN_OV") (class "Default")
      (node (ref "UNN") (pin "7") (pinfunction "OUTB_7") (pintype "output"))
      (node (ref "X-NORTH") (pin "3") (pinfunction "3_3") (pintype "bidirectional"))
    )
    (net (code "104") (name "N_VN_UV") (class "Default")
      (node (ref "UNN") (pin "1") (pinfunction "OUTA_1") (pintype "output"))
      (node (ref "X-NORTH") (pin "9") (pinfunction "9_9") (pintype "bidirectional"))
    )
    (net (code "105") (name "N_VW") (class "Default")
      (node (ref "C57") (pin "1") (pinfunction "1_1") (pintype "passive"))
      (node (ref "C58") (pin "1") (pinfunction "1_1") (pintype "passive"))
      (node (ref "C92") (pin "1") (pinfunction "1_1") (pintype "passive"))
      (node (ref "SENSOR") (pin "E2") (pinfunction "VDD_RES_E2") (pintype "power_in"))
      (node (ref "SENSOR") (pin "G4") (pinfunction "VDD_RES_G4") (pintype "power_in"))
      (node (ref "TP8") (pin "TP") (pinfunction "TP_TP") (pintype "input"))
      (node (ref "X-NORTH") (pin "13") (pinfunction "13_13") (pintype "bidirectional"))
      (node (ref "X-NORTH") (pin "19") (pinfunction "19_19") (pintype "bidirectional"))
      (node (ref "X-NORTH") (pin "25") (pinfunction "25_25") (pintype "bidirectional"))
      (node (ref "X-NORTH") (pin "31") (pinfunction "31_31") (pintype "bidirectional"))
      (node (ref "X-NORTH") (pin "37") (pinfunction "37_37") (pintype "bidirectional"))
    )
    (net (code "106") (name "N_VW_CV") (class "Default")
      (node (ref "C8") (pin "1") (pinfunction "1_1") (pintype "passive"))
      (node (ref "R1") (pin "1") (pinfunction "1_1") (pintype "passive"))
      (node (ref "X-NORTH") (pin "2") (pinfunction "2_2") (pintype "bidirectional"))
    )
    (net (code "107") (name "N_VW_OV") (class "Default")
      (node (ref "UNW") (pin "7") (pinfunction "OUTB_7") (pintype "output"))
      (node (ref "X-NORTH") (pin "1") (pinfunction "1_1") (pintype "bidirectional"))
    )
    (net (code "108") (name "N_VW_UV") (class "Default")
      (node (ref "UNW") (pin "1") (pinfunction "OUTA_1") (pintype "output"))
      (node (ref "X-NORTH") (pin "7") (pinfunction "7_7") (pintype "bidirectional"))
    )
    (net (code "109") (name "Net-(SENSORB-CMDN)") (class "Default")
      (node (ref "C61") (pin "1") (pinfunction "1_1") (pintype "passive"))
      (node (ref "SENSOR") (pin "F1") (pinfunction "CMDN_F1") (pintype "bidirectional"))
    )
    (net (code "110") (name "Net-(SENSORB-CMDP)") (class "Default")
      (node (ref "C22") (pin "2") (pinfunction "2_2") (pintype "passive"))
      (node (ref "SENSOR") (pin "F2") (pinfunction "CMDP_F2") (pintype "bidirectional"))
    )
    (net (code "111") (name "Net-(SENSORB-CMDP_COMP)") (class "Default")
      (node (ref "C28") (pin "2") (pinfunction "2_2") (pintype "passive"))
      (node (ref "SENSOR") (pin "H3") (pinfunction "CMDP_COMP_H3") (pintype "bidirectional"))
    )
    (net (code "112") (name "Net-(SENSORB-CMDP_COMP_INV)") (class "Default")
      (node (ref "C27") (pin "2") (pinfunction "2_2") (pintype "passive"))
      (node (ref "SENSOR") (pin "F3") (pinfunction "CMDP_COMP_INV_F3") (pintype "bidirectional"))
    )
    (net (code "113") (name "Net-(SENSORB-CMD_COLAMP)") (class "Default")
      (node (ref "C25") (pin "2") (pinfunction "2_2") (pintype "passive"))
      (node (ref "SENSOR") (pin "C6") (pinfunction "CMD_COLAMP_C6") (pintype "bidirectional"))
    )
    (net (code "114") (name "Net-(SENSORB-CMD_COL_LOAD)") (class "Default")
      (node (ref "C23") (pin "2") (pinfunction "2_2") (pintype "passive"))
      (node (ref "SENSOR") (pin "B1") (pinfunction "CMD_COL_LOAD_B1") (pintype "bidirectional"))
    )
    (net (code "115") (name "Net-(SENSORB-CMD_COL_PC)") (class "Default")
      (node (ref "C26") (pin "2") (pinfunction "2_2") (pintype "passive"))
      (node (ref "SENSOR") (pin "D1") (pinfunction "CMD_COL_PC_D1") (pintype "bidirectional"))
    )
    (net (code "116") (name "Net-(SENSORB-CMD_LVDS)") (class "Default")
      (node (ref "C62") (pin "1") (pinfunction "1_1") (pintype "passive"))
      (node (ref "SENSOR") (pin "C1") (pinfunction "CMD_LVDS_C1") (pintype "bidirectional"))
    )
    (net (code "117") (name "Net-(SENSORB-CMD_RAMP)") (class "Default")
      (node (ref "C24") (pin "2") (pinfunction "2_2") (pintype "passive"))
      (node (ref "SENSOR") (pin "B29") (pinfunction "CMD_RAMP_B29") (pintype "bidirectional"))
    )
    (net (code "118") (name "Net-(SENSORB-VBGAP)") (class "Default")
      (node (ref "C64") (pin "1") (pinfunction "1_1") (pintype "passive"))
      (node (ref "SENSOR") (pin "C29") (pinfunction "VBGAP_C29") (pintype "bidirectional"))
    )
    (net (code "119") (name "Net-(SENSORB-VCLAMP)") (class "Default")
      (node (ref "C63") (pin "1") (pinfunction "1_1") (pintype "passive"))
      (node (ref "SENSOR") (pin "D4") (pinfunction "VCLAMP_D4") (pintype "bidirectional"))
    )
    (net (code "120") (name "Net-(SENSORB-VCLAMP_ADC)") (class "Default")
      (node (ref "C60") (pin "1") (pinfunction "1_1") (pintype "passive"))
      (node (ref "SENSOR") (pin "G2") (pinfunction "VCLAMP_ADC_G2") (pintype "bidirectional"))
    )
    (net (code "121") (name "Net-(SENSORB-VPCH_H)") (class "Default")
      (node (ref "C71") (pin "1") (pinfunction "1_1") (pintype "passive"))
      (node (ref "SENSOR") (pin "C4") (pinfunction "VPCH_H_C4") (pintype "bidirectional"))
    )
    (net (code "122") (name "Net-(SENSORB-VPCH_L)") (class "Default")
      (node (ref "C14") (pin "1") (pinfunction "1_1") (pintype "passive"))
      (node (ref "SENSOR") (pin "A4") (pinfunction "VPCH_L_A4") (pintype "bidirectional"))
    )
    (net (code "123") (name "Net-(SENSORB-VREF)") (class "Default")
      (node (ref "C29") (pin "1") (pinfunction "1_1") (pintype "passive"))
      (node (ref "SENSOR") (pin "A3") (pinfunction "VREF_A3") (pintype "bidirectional"))
    )
    (net (code "124") (name "Net-(SENSORB-VREF_ADC)") (class "Default")
      (node (ref "C30") (pin "1") (pinfunction "1_1") (pintype "passive"))
      (node (ref "SENSOR") (pin "B3") (pinfunction "VREF_ADC_B3") (pintype "bidirectional"))
    )
    (net (code "125") (name "Net-(SENSORB-VRES_L)") (class "Default")
      (node (ref "C15") (pin "1") (pinfunction "1_1") (pintype "passive"))
      (node (ref "SENSOR") (pin "D5") (pinfunction "VRES_L_D5") (pintype "bidirectional"))
    )
    (net (code "126") (name "Net-(SENSORB-VTF_LOW0)") (class "Default")
      (node (ref "C18") (pin "1") (pinfunction "1_1") (pintype "passive"))
      (node (ref "SENSOR") (pin "C5") (pinfunction "VTF_LOW0_C5") (pintype "bidirectional"))
    )
    (net (code "127") (name "Net-(SENSORB-VTF_LOW1)") (class "Default")
      (node (ref "C19") (pin "1") (pinfunction "1_1") (pintype "passive"))
      (node (ref "SENSOR") (pin "D6") (pinfunction "VTF_LOW1_D6") (pintype "bidirectional"))
    )
    (net (code "128") (name "Net-(SENSORB-VTF_LOW2)") (class "Default")
      (node (ref "C20") (pin "1") (pinfunction "1_1") (pintype "passive"))
      (node (ref "SENSOR") (pin "B30") (pinfunction "VTF_LOW2_B30") (pintype "bidirectional"))
    )
    (net (code "129") (name "Net-(SENSORB-VTF_LOW3)") (class "Default")
      (node (ref "C21") (pin "1") (pinfunction "1_1") (pintype "passive"))
      (node (ref "SENSOR") (pin "C30") (pinfunction "VTF_LOW3_C30") (pintype "bidirectional"))
    )
    (net (code "130") (name "Net-(U3-ADJ)") (class "Default")
      (node (ref "R21") (pin "1") (pinfunction "1_1") (pintype "passive"))
      (node (ref "R22") (pin "2") (pinfunction "2_2") (pintype "passive"))
      (node (ref "U3") (pin "5") (pinfunction "ADJ_5") (pintype "input"))
    )
    (net (code "131") (name "Net-(U6-B4)") (class "Default")
      (node (ref "TP9") (pin "TP") (pinfunction "TP_TP") (pintype "input"))
      (node (ref "U6") (pin "9") (pinfunction "B4_9") (pintype "bidirectional"))
    )
    (net (code "132") (name "Net-(UEP-WP)") (class "Default")
      (node (ref "R1X") (pin "2") (pinfunction "2_2") (pintype "passive"))
      (node (ref "R2X") (pin "1") (pinfunction "1_1") (pintype "passive"))
      (node (ref "UEP") (pin "7") (pinfunction "WP_7") (pintype "input"))
    )
    (net (code "133") (name "Net-(UNE-VINA+)") (class "Default")
      (node (ref "R7") (pin "2") (pinfunction "2_2") (pintype "passive"))
      (node (ref "R8") (pin "1") (pinfunction "1_1") (pintype "passive"))
      (node (ref "UNE") (pin "3") (pinfunction "VINA+_3") (pintype "input"))
    )
    (net (code "134") (name "Net-(UNE-VINB-)") (class "Default")
      (node (ref "R8") (pin "2") (pinfunction "2_2") (pintype "passive"))
      (node (ref "R9") (pin "1") (pinfunction "1_1") (pintype "passive"))
      (node (ref "UNE") (pin "6") (pinfunction "VINB-_6") (pintype "input"))
    )
    (net (code "135") (name "Net-(UNN-VINA+)") (class "Default")
      (node (ref "R4") (pin "2") (pinfunction "2_2") (pintype "passive"))
      (node (ref "R5") (pin "1") (pinfunction "1_1") (pintype "passive"))
      (node (ref "UNN") (pin "3") (pinfunction "VINA+_3") (pintype "input"))
    )
    (net (code "136") (name "Net-(UNN-VINB-)") (class "Default")
      (node (ref "R5") (pin "2") (pinfunction "2_2") (pintype "passive"))
      (node (ref "R6") (pin "1") (pinfunction "1_1") (pintype "passive"))
      (node (ref "UNN") (pin "6") (pinfunction "VINB-_6") (pintype "input"))
    )
    (net (code "137") (name "Net-(UNW-VINA+)") (class "Default")
      (node (ref "R1") (pin "2") (pinfunction "2_2") (pintype "passive"))
      (node (ref "R2") (pin "1") (pinfunction "1_1") (pintype "passive"))
      (node (ref "UNW") (pin "3") (pinfunction "VINA+_3") (pintype "input"))
    )
    (net (code "138") (name "Net-(UNW-VINB-)") (class "Default")
      (node (ref "R2") (pin "2") (pinfunction "2_2") (pintype "passive"))
      (node (ref "R3") (pin "1") (pinfunction "1_1") (pintype "passive"))
      (node (ref "UNW") (pin "6") (pinfunction "VINB-_6") (pintype "input"))
    )
    (net (code "139") (name "Net-(USE-VINA+)") (class "Default")
      (node (ref "R10") (pin "2") (pinfunction "2_2") (pintype "passive"))
      (node (ref "R11") (pin "1") (pinfunction "1_1") (pintype "passive"))
      (node (ref "USE") (pin "3") (pinfunction "VINA+_3") (pintype "input"))
    )
    (net (code "140") (name "Net-(USE-VINB-)") (class "Default")
      (node (ref "R11") (pin "2") (pinfunction "2_2") (pintype "passive"))
      (node (ref "R12") (pin "1") (pinfunction "1_1") (pintype "passive"))
      (node (ref "USE") (pin "6") (pinfunction "VINB-_6") (pintype "input"))
    )
    (net (code "141") (name "Net-(USS-VINA+)") (class "Default")
      (node (ref "R13") (pin "2") (pinfunction "2_2") (pintype "passive"))
      (node (ref "R14") (pin "1") (pinfunction "1_1") (pintype "passive"))
      (node (ref "USS") (pin "3") (pinfunction "VINA+_3") (pintype "input"))
    )
    (net (code "142") (name "Net-(USS-VINB-)") (class "Default")
      (node (ref "R14") (pin "2") (pinfunction "2_2") (pintype "passive"))
      (node (ref "R15") (pin "1") (pinfunction "1_1") (pintype "passive"))
      (node (ref "USS") (pin "6") (pinfunction "VINB-_6") (pintype "input"))
    )
    (net (code "143") (name "Net-(USW-VINA+)") (class "Default")
      (node (ref "R16") (pin "2") (pinfunction "2_2") (pintype "passive"))
      (node (ref "R17") (pin "1") (pinfunction "1_1") (pintype "passive"))
      (node (ref "USW") (pin "3") (pinfunction "VINA+_3") (pintype "input"))
    )
    (net (code "144") (name "Net-(USW-VINB-)") (class "Default")
      (node (ref "R17") (pin "2") (pinfunction "2_2") (pintype "passive"))
      (node (ref "R18") (pin "1") (pinfunction "1_1") (pintype "passive"))
      (node (ref "USW") (pin "6") (pinfunction "VINB-_6") (pintype "input"))
    )
    (net (code "145") (name "S00_N") (class "Default")
      (node (ref "X-SOUTH") (pin "16") (pinfunction "16_16") (pintype "bidirectional"))
    )
    (net (code "146") (name "S00_P") (class "Default")
      (node (ref "X-SOUTH") (pin "14") (pinfunction "14_14") (pintype "bidirectional"))
    )
    (net (code "147") (name "S01_N") (class "Default")
      (node (ref "X-SOUTH") (pin "17") (pinfunction "17_17") (pintype "bidirectional"))
    )
    (net (code "148") (name "S01_P") (class "Default")
      (node (ref "X-SOUTH") (pin "15") (pinfunction "15_15") (pintype "bidirectional"))
    )
    (net (code "149") (name "S02_N") (class "Default")
      (node (ref "X-SOUTH") (pin "22") (pinfunction "22_22") (pintype "bidirectional"))
    )
    (net (code "150") (name "S02_P") (class "Default")
      (node (ref "X-SOUTH") (pin "20") (pinfunction "20_20") (pintype "bidirectional"))
    )
    (net (code "151") (name "S03_N") (class "Default")
      (node (ref "X-SOUTH") (pin "23") (pinfunction "23_23") (pintype "bidirectional"))
    )
    (net (code "152") (name "S03_P") (class "Default")
      (node (ref "X-SOUTH") (pin "21") (pinfunction "21_21") (pintype "bidirectional"))
    )
    (net (code "153") (name "S04_N") (class "Default")
      (node (ref "SENSOR") (pin "C24") (pinfunction "OUT32_N_C24") (pintype "output"))
      (node (ref "X-SOUTH") (pin "28") (pinfunction "28_28") (pintype "bidirectional"))
    )
    (net (code "154") (name "S04_P") (class "Default")
      (node (ref "SENSOR") (pin "C25") (pinfunction "OUT32_P_C25") (pintype "output"))
      (node (ref "X-SOUTH") (pin "26") (pinfunction "26_26") (pintype "bidirectional"))
    )
    (net (code "155") (name "S05_N") (class "Default")
      (node (ref "X-SOUTH") (pin "29") (pinfunction "29_29") (pintype "bidirectional"))
    )
    (net (code "156") (name "S05_P") (class "Default")
      (node (ref "X-SOUTH") (pin "27") (pinfunction "27_27") (pintype "bidirectional"))
    )
    (net (code "157") (name "S06_N") (class "Default")
      (node (ref "SENSOR") (pin "D23") (pinfunction "OUT30_N_D23") (pintype "output"))
      (node (ref "X-SOUTH") (pin "34") (pinfunction "34_34") (pintype "bidirectional"))
    )
    (net (code "158") (name "S06_P") (class "Default")
      (node (ref "SENSOR") (pin "D24") (pinfunction "OUT30_P_D24") (pintype "output"))
      (node (ref "X-SOUTH") (pin "32") (pinfunction "32_32") (pintype "bidirectional"))
    )
    (net (code "159") (name "S07_N") (class "Default")
      (node (ref "SENSOR") (pin "B24") (pinfunction "OUT31_N_B24") (pintype "output"))
      (node (ref "X-SOUTH") (pin "35") (pinfunction "35_35") (pintype "bidirectional"))
    )
    (net (code "160") (name "S07_P") (class "Default")
      (node (ref "SENSOR") (pin "B25") (pinfunction "OUT31_P_B25") (pintype "output"))
      (node (ref "X-SOUTH") (pin "33") (pinfunction "33_33") (pintype "bidirectional"))
    )
    (net (code "161") (name "S08_N") (class "Default")
      (node (ref "SENSOR") (pin "D21") (pinfunction "OUT27_N_D21") (pintype "output"))
      (node (ref "X-SOUTH") (pin "40") (pinfunction "40_40") (pintype "bidirectional"))
    )
    (net (code "162") (name "S08_P") (class "Default")
      (node (ref "SENSOR") (pin "D22") (pinfunction "OUT27_P_D22") (pintype "output"))
      (node (ref "X-SOUTH") (pin "38") (pinfunction "38_38") (pintype "bidirectional"))
    )
    (net (code "163") (name "S09_N") (class "Default")
      (node (ref "SENSOR") (pin "A23") (pinfunction "OUT29_N_A23") (pintype "output"))
      (node (ref "X-SOUTH") (pin "41") (pinfunction "41_41") (pintype "bidirectional"))
    )
    (net (code "164") (name "S09_P") (class "Default")
      (node (ref "SENSOR") (pin "A24") (pinfunction "OUT29_P_A24") (pintype "output"))
      (node (ref "X-SOUTH") (pin "39") (pinfunction "39_39") (pintype "bidirectional"))
    )
    (net (code "165") (name "S10_N") (class "Default")
      (node (ref "SENSOR") (pin "C21") (pinfunction "OUT28_N_C21") (pintype "output"))
      (node (ref "X-SOUTH") (pin "46") (pinfunction "46_46") (pintype "bidirectional"))
    )
    (net (code "166") (name "S10_P") (class "Default")
      (node (ref "SENSOR") (pin "C22") (pinfunction "OUT28_P_C22") (pintype "output"))
      (node (ref "X-SOUTH") (pin "44") (pinfunction "44_44") (pintype "bidirectional"))
    )
    (net (code "167") (name "S11_N") (class "Default")
      (node (ref "SENSOR") (pin "B20") (pinfunction "OUT26_N_B20") (pintype "output"))
      (node (ref "X-SOUTH") (pin "47") (pinfunction "47_47") (pintype "bidirectional"))
    )
    (net (code "168") (name "S11_P") (class "Default")
      (node (ref "SENSOR") (pin "B21") (pinfunction "OUT26_P_B21") (pintype "output"))
      (node (ref "X-SOUTH") (pin "45") (pinfunction "45_45") (pintype "bidirectional"))
    )
    (net (code "169") (name "S12_N") (class "Default")
      (node (ref "SENSOR") (pin "D19") (pinfunction "OUT24_N_D19") (pintype "output"))
      (node (ref "X-SOUTH") (pin "52") (pinfunction "52_52") (pintype "bidirectional"))
    )
    (net (code "170") (name "S12_P") (class "Default")
      (node (ref "SENSOR") (pin "D20") (pinfunction "OUT24_P_D20") (pintype "output"))
      (node (ref "X-SOUTH") (pin "50") (pinfunction "50_50") (pintype "bidirectional"))
    )
    (net (code "171") (name "S13_N") (class "Default")
      (node (ref "SENSOR") (pin "A19") (pinfunction "OUT23_N_A19") (pintype "output"))
      (node (ref "X-SOUTH") (pin "53") (pinfunction "53_53") (pintype "bidirectional"))
    )
    (net (code "172") (name "S13_P") (class "Default")
      (node (ref "SENSOR") (pin "A20") (pinfunction "OUT23_P_A20") (pintype "output"))
      (node (ref "X-SOUTH") (pin "51") (pinfunction "51_51") (pintype "bidirectional"))
    )
    (net (code "173") (name "S14_N") (class "Default")
      (node (ref "SENSOR") (pin "C19") (pinfunction "OUT25_N_C19") (pintype "output"))
      (node (ref "X-SOUTH") (pin "58") (pinfunction "58_58") (pintype "bidirectional"))
    )
    (net (code "174") (name "S14_P") (class "Default")
      (node (ref "SENSOR") (pin "C20") (pinfunction "OUT25_P_C20") (pintype "output"))
      (node (ref "X-SOUTH") (pin "56") (pinfunction "56_56") (pintype "bidirectional"))
    )
    (net (code "175") (name "S15_N") (class "Default")
      (node (ref "SENSOR") (pin "B18") (pinfunction "OUT22_N_B18") (pintype "output"))
      (node (ref "X-SOUTH") (pin "59") (pinfunction "59_59") (pintype "bidirectional"))
    )
    (net (code "176") (name "S15_P") (class "Default")
      (node (ref "SENSOR") (pin "B19") (pinfunction "OUT22_P_B19") (pintype "output"))
      (node (ref "X-SOUTH") (pin "57") (pinfunction "57_57") (pintype "bidirectional"))
    )
    (net (code "177") (name "S16_N") (class "Default")
      (node (ref "SENSOR") (pin "C17") (pinfunction "OUT21_N_C17") (pintype "output"))
      (node (ref "X-SOUTH") (pin "64") (pinfunction "64_64") (pintype "bidirectional"))
    )
    (net (code "178") (name "S16_P") (class "Default")
      (node (ref "SENSOR") (pin "C18") (pinfunction "OUT21_P_C18") (pintype "output"))
      (node (ref "X-SOUTH") (pin "62") (pinfunction "62_62") (pintype "bidirectional"))
    )
    (net (code "179") (name "S17_N") (class "Default")
      (node (ref "SENSOR") (pin "A17") (pinfunction "OUT19_N_A17") (pintype "output"))
      (node (ref "X-SOUTH") (pin "65") (pinfunction "65_65") (pintype "bidirectional"))
    )
    (net (code "180") (name "S17_P") (class "Default")
      (node (ref "SENSOR") (pin "A18") (pinfunction "OUT19_P_A18") (pintype "output"))
      (node (ref "X-SOUTH") (pin "63") (pinfunction "63_63") (pintype "bidirectional"))
    )
    (net (code "181") (name "S18_N") (class "Default")
      (node (ref "SENSOR") (pin "D17") (pinfunction "OUT20_N_D17") (pintype "output"))
      (node (ref "X-SOUTH") (pin "70") (pinfunction "70_70") (pintype "bidirectional"))
    )
    (net (code "182") (name "S18_P") (class "Default")
      (node (ref "SENSOR") (pin "D18") (pinfunction "OUT20_P_D18") (pintype "output"))
      (node (ref "X-SOUTH") (pin "68") (pinfunction "68_68") (pintype "bidirectional"))
    )
    (net (code "183") (name "S19_N") (class "Default")
      (node (ref "SENSOR") (pin "B16") (pinfunction "OUT18_N_B16") (pintype "output"))
      (node (ref "X-SOUTH") (pin "71") (pinfunction "71_71") (pintype "bidirectional"))
    )
    (net (code "184") (name "S19_P") (class "Default")
      (node (ref "SENSOR") (pin "B17") (pinfunction "OUT18_P_B17") (pintype "output"))
      (node (ref "X-SOUTH") (pin "69") (pinfunction "69_69") (pintype "bidirectional"))
    )
    (net (code "185") (name "S20_N") (class "Default")
      (node (ref "SENSOR") (pin "D15") (pinfunction "OUT17_N_D15") (pintype "output"))
      (node (ref "X-SOUTH") (pin "76") (pinfunction "76_76") (pintype "bidirectional"))
    )
    (net (code "186") (name "S20_P") (class "Default")
      (node (ref "SENSOR") (pin "D16") (pinfunction "OUT17_P_D16") (pintype "output"))
      (node (ref "X-SOUTH") (pin "74") (pinfunction "74_74") (pintype "bidirectional"))
    )
    (net (code "187") (name "S21_N") (class "Default")
      (node (ref "SENSOR") (pin "B14") (pinfunction "OUT16_N_B14") (pintype "output"))
      (node (ref "X-SOUTH") (pin "77") (pinfunction "77_77") (pintype "bidirectional"))
    )
    (net (code "188") (name "S21_P") (class "Default")
      (node (ref "SENSOR") (pin "B15") (pinfunction "OUT16_P_B15") (pintype "output"))
      (node (ref "X-SOUTH") (pin "75") (pinfunction "75_75") (pintype "bidirectional"))
    )
    (net (code "189") (name "S22_N") (class "Default")
      (node (ref "SENSOR") (pin "D13") (pinfunction "OUT15_N_D13") (pintype "output"))
      (node (ref "X-SOUTH") (pin "82") (pinfunction "82_82") (pintype "bidirectional"))
    )
    (net (code "190") (name "S22_P") (class "Default")
      (node (ref "SENSOR") (pin "D14") (pinfunction "OUT15_P_D14") (pintype "output"))
      (node (ref "X-SOUTH") (pin "80") (pinfunction "80_80") (pintype "bidirectional"))
    )
    (net (code "191") (name "S23_N") (class "Default")
      (node (ref "SENSOR") (pin "A13") (pinfunction "OUT13_N_A13") (pintype "output"))
      (node (ref "X-SOUTH") (pin "83") (pinfunction "83_83") (pintype "bidirectional"))
    )
    (net (code "192") (name "S23_P") (class "Default")
      (node (ref "SENSOR") (pin "A14") (pinfunction "OUT13_P_A14") (pintype "output"))
      (node (ref "X-SOUTH") (pin "81") (pinfunction "81_81") (pintype "bidirectional"))
    )
    (net (code "193") (name "S24_N") (class "Default")
      (node (ref "SENSOR") (pin "C13") (pinfunction "OUT14_N_C13") (pintype "output"))
      (node (ref "X-SOUTH") (pin "88") (pinfunction "88_88") (pintype "bidirectional"))
    )
    (net (code "194") (name "S24_P") (class "Default")
      (node (ref "SENSOR") (pin "C14") (pinfunction "OUT14_P_C14") (pintype "output"))
      (node (ref "X-SOUTH") (pin "86") (pinfunction "86_86") (pintype "bidirectional"))
    )
    (net (code "195") (name "S25_N") (class "Default")
      (node (ref "SENSOR") (pin "B12") (pinfunction "OUT12_N_B12") (pintype "output"))
      (node (ref "X-SOUTH") (pin "89") (pinfunction "89_89") (pintype "bidirectional"))
    )
    (net (code "196") (name "S25_P") (class "Default")
      (node (ref "SENSOR") (pin "B13") (pinfunction "OUT12_P_B13") (pintype "output"))
      (node (ref "X-SOUTH") (pin "87") (pinfunction "87_87") (pintype "bidirectional"))
    )
    (net (code "197") (name "S26_N") (class "Default")
      (node (ref "SENSOR") (pin "D11") (pinfunction "OUT10_N_D11") (pintype "output"))
      (node (ref "X-SOUTH") (pin "94") (pinfunction "94_94") (pintype "bidirectional"))
    )
    (net (code "198") (name "S26_P") (class "Default")
      (node (ref "SENSOR") (pin "D12") (pinfunction "OUT10_P_D12") (pintype "output"))
      (node (ref "X-SOUTH") (pin "92") (pinfunction "92_92") (pintype "bidirectional"))
    )
    (net (code "199") (name "S27_N") (class "Default")
      (node (ref "SENSOR") (pin "A11") (pinfunction "OUT9_N_A11") (pintype "output"))
      (node (ref "X-SOUTH") (pin "95") (pinfunction "95_95") (pintype "bidirectional"))
    )
    (net (code "200") (name "S27_P") (class "Default")
      (node (ref "SENSOR") (pin "A12") (pinfunction "OUT9_P_A12") (pintype "output"))
      (node (ref "X-SOUTH") (pin "93") (pinfunction "93_93") (pintype "bidirectional"))
    )
    (net (code "201") (name "S28_N") (class "Default")
      (node (ref "SENSOR") (pin "C11") (pinfunction "OUT11_N_C11") (pintype "output"))
      (node (ref "X-SOUTH") (pin "100") (pinfunction "100_100") (pintype "bidirectional"))
    )
    (net (code "202") (name "S28_P") (class "Default")
      (node (ref "SENSOR") (pin "C12") (pinfunction "OUT11_P_C12") (pintype "output"))
      (node (ref "X-SOUTH") (pin "98") (pinfunction "98_98") (pintype "bidirectional"))
    )
    (net (code "203") (name "S29_N") (class "Default")
      (node (ref "SENSOR") (pin "B10") (pinfunction "OUT8_N_B10") (pintype "output"))
      (node (ref "X-SOUTH") (pin "101") (pinfunction "101_101") (pintype "bidirectional"))
    )
    (net (code "204") (name "S29_P") (class "Default")
      (node (ref "SENSOR") (pin "B11") (pinfunction "OUT8_P_B11") (pintype "output"))
      (node (ref "X-SOUTH") (pin "99") (pinfunction "99_99") (pintype "bidirectional"))
    )
    (net (code "205") (name "S30_N") (class "Default")
      (node (ref "SENSOR") (pin "C9") (pinfunction "OUT7_N_C9") (pintype "output"))
      (node (ref "X-SOUTH") (pin "106") (pinfunction "106_106") (pintype "bidirectional"))
    )
    (net (code "206") (name "S30_P") (class "Default")
      (node (ref "SENSOR") (pin "C10") (pinfunction "OUT7_P_C10") (pintype "output"))
      (node (ref "X-SOUTH") (pin "104") (pinfunction "104_104") (pintype "bidirectional"))
    )
    (net (code "207") (name "S31_N") (class "Default")
      (node (ref "SENSOR") (pin "B8") (pinfunction "OUT5_N_B8") (pintype "output"))
      (node (ref "X-SOUTH") (pin "107") (pinfunction "107_107") (pintype "bidirectional"))
    )
    (net (code "208") (name "S31_P") (class "Default")
      (node (ref "SENSOR") (pin "B9") (pinfunction "OUT5_P_B9") (pintype "output"))
      (node (ref "X-SOUTH") (pin "105") (pinfunction "105_105") (pintype "bidirectional"))
    )
    (net (code "209") (name "S32_N") (class "Default")
      (node (ref "SENSOR") (pin "D9") (pinfunction "OUT6_N_D9") (pintype "output"))
      (node (ref "X-SOUTH") (pin "112") (pinfunction "112_112") (pintype "bidirectional"))
    )
    (net (code "210") (name "S32_P") (class "Default")
      (node (ref "SENSOR") (pin "D10") (pinfunction "OUT6_P_D10") (pintype "output"))
      (node (ref "X-SOUTH") (pin "110") (pinfunction "110_110") (pintype "bidirectional"))
    )
    (net (code "211") (name "S33_N") (class "Default")
      (node (ref "SENSOR") (pin "A7") (pinfunction "OUT2_N_A7") (pintype "output"))
      (node (ref "X-SOUTH") (pin "113") (pinfunction "113_113") (pintype "bidirectional"))
    )
    (net (code "212") (name "S33_P") (class "Default")
      (node (ref "SENSOR") (pin "A8") (pinfunction "OUT2_P_A8") (pintype "output"))
      (node (ref "X-SOUTH") (pin "111") (pinfunction "111_111") (pintype "bidirectional"))
    )
    (net (code "213") (name "S34_N") (class "Default")
      (node (ref "SENSOR") (pin "C7") (pinfunction "OUT4_N_C7") (pintype "output"))
      (node (ref "X-SOUTH") (pin "118") (pinfunction "118_118") (pintype "bidirectional"))
    )
    (net (code "214") (name "S34_P") (class "Default")
      (node (ref "SENSOR") (pin "C8") (pinfunction "OUT4_P_C8") (pintype "output"))
      (node (ref "X-SOUTH") (pin "116") (pinfunction "116_116") (pintype "bidirectional"))
    )
    (net (code "215") (name "S35_N") (class "Default")
      (node (ref "SENSOR") (pin "B6") (pinfunction "OUT1_N_B6") (pintype "output"))
      (node (ref "X-SOUTH") (pin "119") (pinfunction "119_119") (pintype "bidirectional"))
    )
    (net (code "216") (name "S35_P") (class "Default")
      (node (ref "SENSOR") (pin "B7") (pinfunction "OUT1_P_B7") (pintype "output"))
      (node (ref "X-SOUTH") (pin "117") (pinfunction "117_117") (pintype "bidirectional"))
    )
    (net (code "217") (name "S36_N") (class "Default")
      (node (ref "SENSOR") (pin "D7") (pinfunction "OUT3_N_D7") (pintype "output"))
      (node (ref "X-SOUTH") (pin "124") (pinfunction "124_124") (pintype "bidirectional"))
    )
    (net (code "218") (name "S36_P") (class "Default")
      (node (ref "SENSOR") (pin "D8") (pinfunction "OUT3_P_D8") (pintype "output"))
      (node (ref "X-SOUTH") (pin "122") (pinfunction "122_122") (pintype "bidirectional"))
    )
    (net (code "219") (name "S37_N") (class "Default")
      (node (ref "SENSOR") (pin "A5") (pinfunction "OUTCTR_N_A5") (pintype "output"))
      (node (ref "X-SOUTH") (pin "125") (pinfunction "125_125") (pintype "bidirectional"))
    )
    (net (code "220") (name "S37_P") (class "Default")
      (node (ref "SENSOR") (pin "A6") (pinfunction "OUTCTR_P_A6") (pintype "output"))
      (node (ref "X-SOUTH") (pin "123") (pinfunction "123_123") (pintype "bidirectional"))
    )
    (net (code "221") (name "S38_N") (class "Default")
      (node (ref "X-SOUTH") (pin "130") (pinfunction "130_130") (pintype "bidirectional"))
    )
    (net (code "222") (name "S38_P") (class "Default")
      (node (ref "X-SOUTH") (pin "128") (pinfunction "128_128") (pintype "bidirectional"))
    )
    (net (code "223") (name "S39_N") (class "Default")
      (node (ref "U3") (pin "6") (pinfunction "EN_6") (pintype "input"))
      (node (ref "X-SOUTH") (pin "131") (pinfunction "131_131") (pintype "bidirectional"))
    )
    (net (code "224") (name "S39_P") (class "Default")
      (node (ref "X-SOUTH") (pin "129") (pinfunction "129_129") (pintype "bidirectional"))
    )
    (net (code "225") (name "SPI_CLK") (class "Default")
      (node (ref "SENSOR") (pin "H29") (pinfunction "SPI_CLK_H29") (pintype "input"))
      (node (ref "U4") (pin "9") (pinfunction "B4_9") (pintype "bidirectional"))
    )
    (net (code "226") (name "SPI_EN") (class "Default")
      (node (ref "SENSOR") (pin "F28") (pinfunction "SPI_EN_F28") (pintype "input"))
      (node (ref "U4") (pin "12") (pinfunction "B1_12") (pintype "bidirectional"))
    )
    (net (code "227") (name "SPI_IN") (class "Default")
      (node (ref "SENSOR") (pin "E28") (pinfunction "SPI_IN_E28") (pintype "input"))
      (node (ref "U4") (pin "10") (pinfunction "B3_10") (pintype "bidirectional"))
    )
    (net (code "228") (name "SPI_OUT") (class "Default")
      (node (ref "SENSOR") (pin "G28") (pinfunction "SPI_OUT_G28") (pintype "output"))
      (node (ref "U4") (pin "11") (pinfunction "B2_11") (pintype "bidirectional"))
    )
    (net (code "229") (name "SYS_RES_N") (class "Default")
      (node (ref "SENSOR") (pin "F30") (pinfunction "SYS_RES_N_F30") (pintype "input"))
      (node (ref "U5") (pin "10") (pinfunction "B3_10") (pintype "bidirectional"))
    )
    (net (code "230") (name "S_CHK_EN") (class "Default")
      (node (ref "X-SOUTH") (pin "8") (pinfunction "8_8") (pintype "bidirectional"))
    )
    (net (code "231") (name "S_CHK_V") (class "Default")
      (node (ref "C5") (pin "1") (pinfunction "1_1") (pintype "passive"))
      (node (ref "C6") (pin "1") (pinfunction "1_1") (pintype "passive"))
      (node (ref "C7") (pin "1") (pinfunction "1_1") (pintype "passive"))
      (node (ref "R20") (pin "1") (pinfunction "1_1") (pintype "passive"))
      (node (ref "TP3") (pin "TP") (pinfunction "TP_TP") (pintype "input"))
      (node (ref "USE") (pin "8") (pinfunction "VDD_8") (pintype "power_in"))
      (node (ref "USS") (pin "8") (pinfunction "VDD_8") (pintype "power_in"))
      (node (ref "USW") (pin "8") (pinfunction "VDD_8") (pintype "power_in"))
      (node (ref "X-SOUTH") (pin "10") (pinfunction "10_10") (pintype "bidirectional"))
    )
    (net (code "232") (name "S_I2C_EN") (class "Default")
      (node (ref "X-SOUTH") (pin "137") (pinfunction "137_137") (pintype "bidirectional"))
    )
    (net (code "233") (name "S_I2C_V") (class "Default")
      (node (ref "U7") (pin "8") (pinfunction "VCC_8") (pintype "power_in"))
      (node (ref "X-SOUTH") (pin "135") (pinfunction "135_135") (pintype "bidirectional"))
    )
    (net (code "234") (name "S_REF") (class "Default")
      (node (ref "R20") (pin "2") (pinfunction "2_2") (pintype "passive"))
      (node (ref "TP4") (pin "TP") (pinfunction "TP_TP") (pintype "input"))
      (node (ref "U2") (pin "1") (pinfunction "CATHODE_1") (pintype "output"))
      (node (ref "U2") (pin "3") (pinfunction "REF_3") (pintype "input"))
      (node (ref "USE") (pin "2") (pinfunction "VINA-_2") (pintype "input"))
      (node (ref "USE") (pin "5") (pinfunction "VINB+_5") (pintype "input"))
      (node (ref "USS") (pin "2") (pinfunction "VINA-_2") (pintype "input"))
      (node (ref "USS") (pin "5") (pinfunction "VINB+_5") (pintype "input"))
      (node (ref "USW") (pin "2") (pinfunction "VINA-_2") (pintype "input"))
      (node (ref "USW") (pin "5") (pinfunction "VINB+_5") (pintype "input"))
    )
    (net (code "235") (name "S_SCK") (class "Default")
      (node (ref "X-SOUTH") (pin "144") (pinfunction "144_144") (pintype "bidirectional"))
    )
    (net (code "236") (name "S_SCL") (class "Default")
      (node (ref "U7") (pin "2") (pinfunction "SCL_2") (pintype "input"))
      (node (ref "X-SOUTH") (pin "143") (pinfunction "143_143") (pintype "bidirectional"))
    )
    (net (code "237") (name "S_SDA") (class "Default")
      (node (ref "U7") (pin "1") (pinfunction "SDA_1") (pintype "bidirectional"))
      (node (ref "X-SOUTH") (pin "141") (pinfunction "141_141") (pintype "bidirectional"))
    )
    (net (code "238") (name "S_SDI") (class "Default")
      (node (ref "X-SOUTH") (pin "140") (pinfunction "140_140") (pintype "bidirectional"))
    )
    (net (code "239") (name "S_SDO") (class "Default")
      (node (ref "X-SOUTH") (pin "142") (pinfunction "142_142") (pintype "bidirectional"))
    )
    (net (code "240") (name "S_SPI_EN") (class "Default")
      (node (ref "X-SOUTH") (pin "136") (pinfunction "136_136") (pintype "bidirectional"))
    )
    (net (code "241") (name "S_SPI_V") (class "Default")
      (node (ref "X-SOUTH") (pin "134") (pinfunction "134_134") (pintype "bidirectional"))
    )
    (net (code "242") (name "S_VE") (class "Default")
      (node (ref "X-SOUTH") (pin "13") (pinfunction "13_13") (pintype "bidirectional"))
      (node (ref "X-SOUTH") (pin "19") (pinfunction "19_19") (pintype "bidirectional"))
      (node (ref "X-SOUTH") (pin "25") (pinfunction "25_25") (pintype "bidirectional"))
      (node (ref "X-SOUTH") (pin "31") (pinfunction "31_31") (pintype "bidirectional"))
      (node (ref "X-SOUTH") (pin "37") (pinfunction "37_37") (pintype "bidirectional"))
    )
    (net (code "243") (name "S_VE_CV") (class "Default")
      (node (ref "C11") (pin "1") (pinfunction "1_1") (pintype "passive"))
      (node (ref "R10") (pin "1") (pinfunction "1_1") (pintype "passive"))
      (node (ref "X-SOUTH") (pin "2") (pinfunction "2_2") (pintype "bidirectional"))
    )
    (net (code "244") (name "S_VE_OV") (class "Default")
      (node (ref "USE") (pin "7") (pinfunction "OUTB_7") (pintype "output"))
      (node (ref "X-SOUTH") (pin "1") (pinfunction "1_1") (pintype "bidirectional"))
    )
    (net (code "245") (name "S_VE_UV") (class "Default")
      (node (ref "USE") (pin "1") (pinfunction "OUTA_1") (pintype "output"))
      (node (ref "X-SOUTH") (pin "7") (pinfunction "7_7") (pintype "bidirectional"))
    )
    (net (code "246") (name "S_VS") (class "Default")
      (node (ref "C45") (pin "1") (pinfunction "1_1") (pintype "passive"))
      (node (ref "C46") (pin "1") (pinfunction "1_1") (pintype "passive"))
      (node (ref "C47") (pin "1") (pinfunction "1_1") (pintype "passive"))
      (node (ref "C48") (pin "1") (pinfunction "1_1") (pintype "passive"))
      (node (ref "C49") (pin "1") (pinfunction "1_1") (pintype "passive"))
      (node (ref "C72") (pin "1") (pinfunction "1_1") (pintype "passive"))
      (node (ref "C73") (pin "1") (pinfunction "1_1") (pintype "passive"))
      (node (ref "C74") (pin "1") (pinfunction "1_1") (pintype "passive"))
      (node (ref "C81") (pin "1") (pinfunction "1_1") (pintype "passive"))
      (node (ref "C82") (pin "1") (pinfunction "1_1") (pintype "passive"))
      (node (ref "C83") (pin "1") (pinfunction "1_1") (pintype "passive"))
      (node (ref "SENSOR") (pin "A30") (pinfunction "VDD_PIX_A30") (pintype "power_in"))
      (node (ref "SENSOR") (pin "D28") (pinfunction "VDD_PIX_D28") (pintype "power_in"))
      (node (ref "SENSOR") (pin "D30") (pinfunction "VDD_PIX_D30") (pintype "power_in"))
      (node (ref "SENSOR") (pin "G1") (pinfunction "VDD_PIX_G1") (pintype "power_in"))
      (node (ref "SENSOR") (pin "H28") (pinfunction "VDD_PIX_H28") (pintype "power_in"))
      (node (ref "TP6") (pin "TP") (pinfunction "TP_TP") (pintype "input"))
      (node (ref "X-SOUTH") (pin "49") (pinfunction "49_49") (pintype "bidirectional"))
      (node (ref "X-SOUTH") (pin "55") (pinfunction "55_55") (pintype "bidirectional"))
      (node (ref "X-SOUTH") (pin "61") (pinfunction "61_61") (pintype "bidirectional"))
      (node (ref "X-SOUTH") (pin "67") (pinfunction "67_67") (pintype "bidirectional"))
      (node (ref "X-SOUTH") (pin "73") (pinfunction "73_73") (pintype "bidirectional"))
      (node (ref "X-SOUTH") (pin "79") (pinfunction "79_79") (pintype "bidirectional"))
      (node (ref "X-SOUTH") (pin "85") (pinfunction "85_85") (pintype "bidirectional"))
      (node (ref "X-SOUTH") (pin "91") (pinfunction "91_91") (pintype "bidirectional"))
      (node (ref "X-SOUTH") (pin "97") (pinfunction "97_97") (pintype "bidirectional"))
    )
    (net (code "247") (name "S_VS_CV") (class "Default")
      (node (ref "C12") (pin "1") (pinfunction "1_1") (pintype "passive"))
      (node (ref "R13") (pin "1") (pinfunction "1_1") (pintype "passive"))
      (node (ref "X-SOUTH") (pin "4") (pinfunction "4_4") (pintype "bidirectional"))
    )
    (net (code "248") (name "S_VS_OV") (class "Default")
      (node (ref "USS") (pin "7") (pinfunction "OUTB_7") (pintype "output"))
      (node (ref "X-SOUTH") (pin "3") (pinfunction "3_3") (pintype "bidirectional"))
    )
    (net (code "249") (name "S_VS_UV") (class "Default")
      (node (ref "USS") (pin "1") (pinfunction "OUTA_1") (pintype "output"))
      (node (ref "X-SOUTH") (pin "9") (pinfunction "9_9") (pintype "bidirectional"))
    )
    (net (code "250") (name "S_VW") (class "Default")
      (node (ref "C90") (pin "1") (pinfunction "1_1") (pintype "passive"))
      (node (ref "U3") (pin "1") (pinfunction "BIAS_1") (pintype "power_in"))
      (node (ref "U3") (pin "3") (pinfunction "IN_3") (pintype "power_in"))
      (node (ref "X-SOUTH") (pin "109") (pinfunction "109_109") (pintype "bidirectional"))
      (node (ref "X-SOUTH") (pin "115") (pinfunction "115_115") (pintype "bidirectional"))
      (node (ref "X-SOUTH") (pin "121") (pinfunction "121_121") (pintype "bidirectional"))
      (node (ref "X-SOUTH") (pin "127") (pinfunction "127_127") (pintype "bidirectional"))
      (node (ref "X-SOUTH") (pin "133") (pinfunction "133_133") (pintype "bidirectional"))
    )
    (net (code "251") (name "S_VW_CV") (class "Default")
      (node (ref "C13") (pin "1") (pinfunction "1_1") (pintype "passive"))
      (node (ref "R16") (pin "1") (pinfunction "1_1") (pintype "passive"))
      (node (ref "X-SOUTH") (pin "6") (pinfunction "6_6") (pintype "bidirectional"))
    )
    (net (code "252") (name "S_VW_OV") (class "Default")
      (node (ref "USW") (pin "7") (pinfunction "OUTB_7") (pintype "output"))
      (node (ref "X-SOUTH") (pin "5") (pinfunction "5_5") (pintype "bidirectional"))
    )
    (net (code "253") (name "S_VW_UV") (class "Default")
      (node (ref "USW") (pin "1") (pinfunction "OUTA_1") (pintype "output"))
      (node (ref "X-SOUTH") (pin "11") (pinfunction "11_11") (pintype "bidirectional"))
    )
    (net (code "254") (name "TDIG1") (class "Default")
      (node (ref "SENSOR") (pin "G27") (pinfunction "TDIG1_G27") (pintype "output"))
      (node (ref "U5") (pin "9") (pinfunction "B4_9") (pintype "bidirectional"))
    )
    (net (code "255") (name "TDIG2") (class "Default")
      (node (ref "SENSOR") (pin "G26") (pinfunction "TDIG2_G26") (pintype "output"))
      (node (ref "U6") (pin "11") (pinfunction "B2_11") (pintype "bidirectional"))
    )
    (net (code "256") (name "T_EXP1") (class "Default")
      (node (ref "SENSOR") (pin "H30") (pinfunction "T_EXP1_H30") (pintype "input"))
      (node (ref "U5") (pin "12") (pinfunction "B1_12") (pintype "bidirectional"))
    )
    (net (code "257") (name "T_EXP2") (class "Default")
      (node (ref "SENSOR") (pin "E29") (pinfunction "T_EXP2_E29") (pintype "input"))
      (node (ref "U6") (pin "10") (pinfunction "B3_10") (pintype "bidirectional"))
    )
    (net (code "258") (name "VRAMP1") (class "Default")
      (node (ref "C16") (pin "1") (pinfunction "1_1") (pintype "passive"))
      (node (ref "R23") (pin "1") (pinfunction "1_1") (pintype "passive"))
      (node (ref "SENSOR") (pin "G29") (pinfunction "VRAMP1_G29") (pintype "bidirectional"))
    )
    (net (code "259") (name "VRAMP2") (class "Default")
      (node (ref "C17") (pin "1") (pinfunction "1_1") (pintype "passive"))
      (node (ref "R23") (pin "2") (pinfunction "2_2") (pintype "passive"))
      (node (ref "SENSOR") (pin "F29") (pinfunction "VRAMP2_F29") (pintype "bidirectional"))
    )
    (net (code "260") (name "VTREF") (class "Default")
      (node (ref "C65") (pin "1") (pinfunction "1_1") (pintype "passive"))
      (node (ref "C91") (pin "2") (pinfunction "2_2") (pintype "passive"))
      (node (ref "R21") (pin "2") (pinfunction "2_2") (pintype "passive"))
      (node (ref "R24") (pin "1") (pinfunction "1_1") (pintype "passive"))
      (node (ref "SENSOR") (pin "B2") (pinfunction "VTREF_B2") (pintype "bidirectional"))
      (node (ref "U3") (pin "4") (pinfunction "OUT_4") (pintype "power_in"))
    )
    (net (code "261") (name "VTSIG") (class "Default")
      (node (ref "C66") (pin "1") (pinfunction "1_1") (pintype "passive"))
      (node (ref "R24") (pin "2") (pinfunction "2_2") (pintype "passive"))
      (node (ref "SENSOR") (pin "C2") (pinfunction "VTSIG_C2") (pintype "bidirectional"))
    )
    (net (code "262") (name "unconnected-(U1-NC-Pad2)") (class "Default")
      (node (ref "U1") (pin "2") (pinfunction "NC_2") (pintype "no_connect"))
    )
    (net (code "263") (name "unconnected-(U1-NC-Pad4)") (class "Default")
      (node (ref "U1") (pin "4") (pinfunction "NC_4") (pintype "no_connect"))
    )
    (net (code "264") (name "unconnected-(U1-NC-Pad5)") (class "Default")
      (node (ref "U1") (pin "5") (pinfunction "NC_5") (pintype "no_connect"))
    )
    (net (code "265") (name "unconnected-(U2-NC-Pad2)") (class "Default")
      (node (ref "U2") (pin "2") (pinfunction "NC_2") (pintype "no_connect"))
    )
    (net (code "266") (name "unconnected-(U2-NC-Pad4)") (class "Default")
      (node (ref "U2") (pin "4") (pinfunction "NC_4") (pintype "no_connect"))
    )
    (net (code "267") (name "unconnected-(U2-NC-Pad5)") (class "Default")
      (node (ref "U2") (pin "5") (pinfunction "NC_5") (pintype "no_connect"))
    )
    (net (code "268") (name "unconnected-(U7-OS-Pad3)") (class "Default")
      (node (ref "U7") (pin "3") (pinfunction "OS_3") (pintype "output"))
    )
    (net (code "269") (name "unconnected-(X-NORTH-PadM1)") (class "Default")
      (node (ref "X-NORTH") (pin "M1") (pinfunction "M1_M1") (pintype "bidirectional"))
    )
    (net (code "270") (name "unconnected-(X-NORTH-PadM2)") (class "Default")
      (node (ref "X-NORTH") (pin "M2") (pinfunction "M2_M2") (pintype "bidirectional"))
    )
    (net (code "271") (name "unconnected-(X-SOUTH-PadM1)") (class "Default")
      (node (ref "X-SOUTH") (pin "M1") (pinfunction "M1_M1") (pintype "bidirectional"))
    )
    (net (code "272") (name "unconnected-(X-SOUTH-PadM2)") (class "Default")
      (node (ref "X-SOUTH") (pin "M2") (pinfunction "M2_M2") (pintype "bidirectional"))
    )
  )
)
